# F6779_Ver_2_1.net
KiCad netlist of a schematic drawn in EAGLE
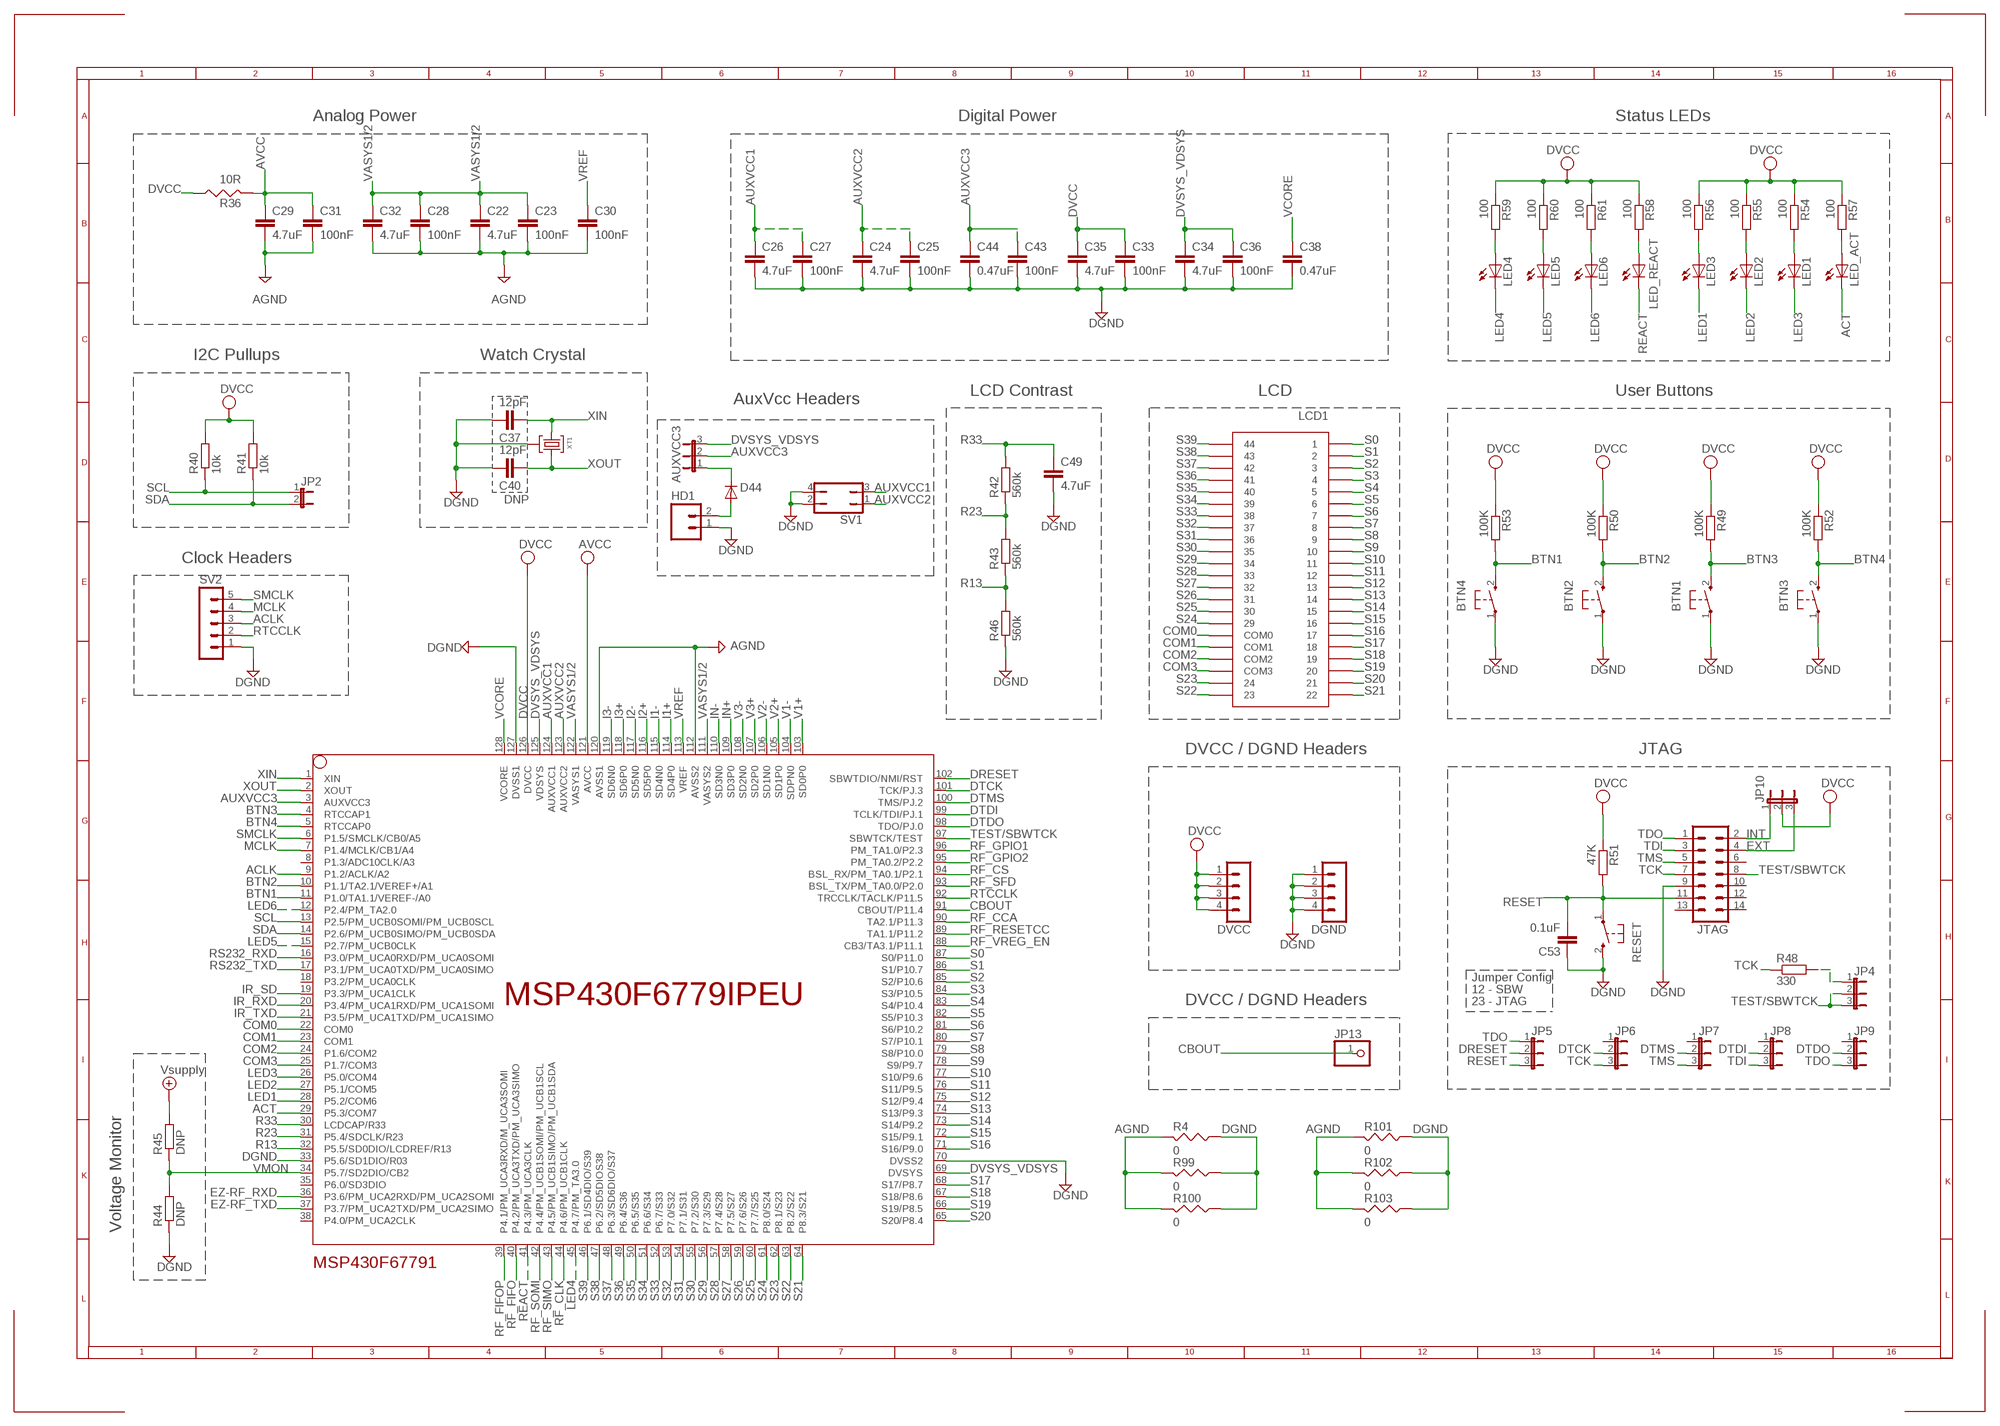
[diagram p0: schematic, sheet 1]
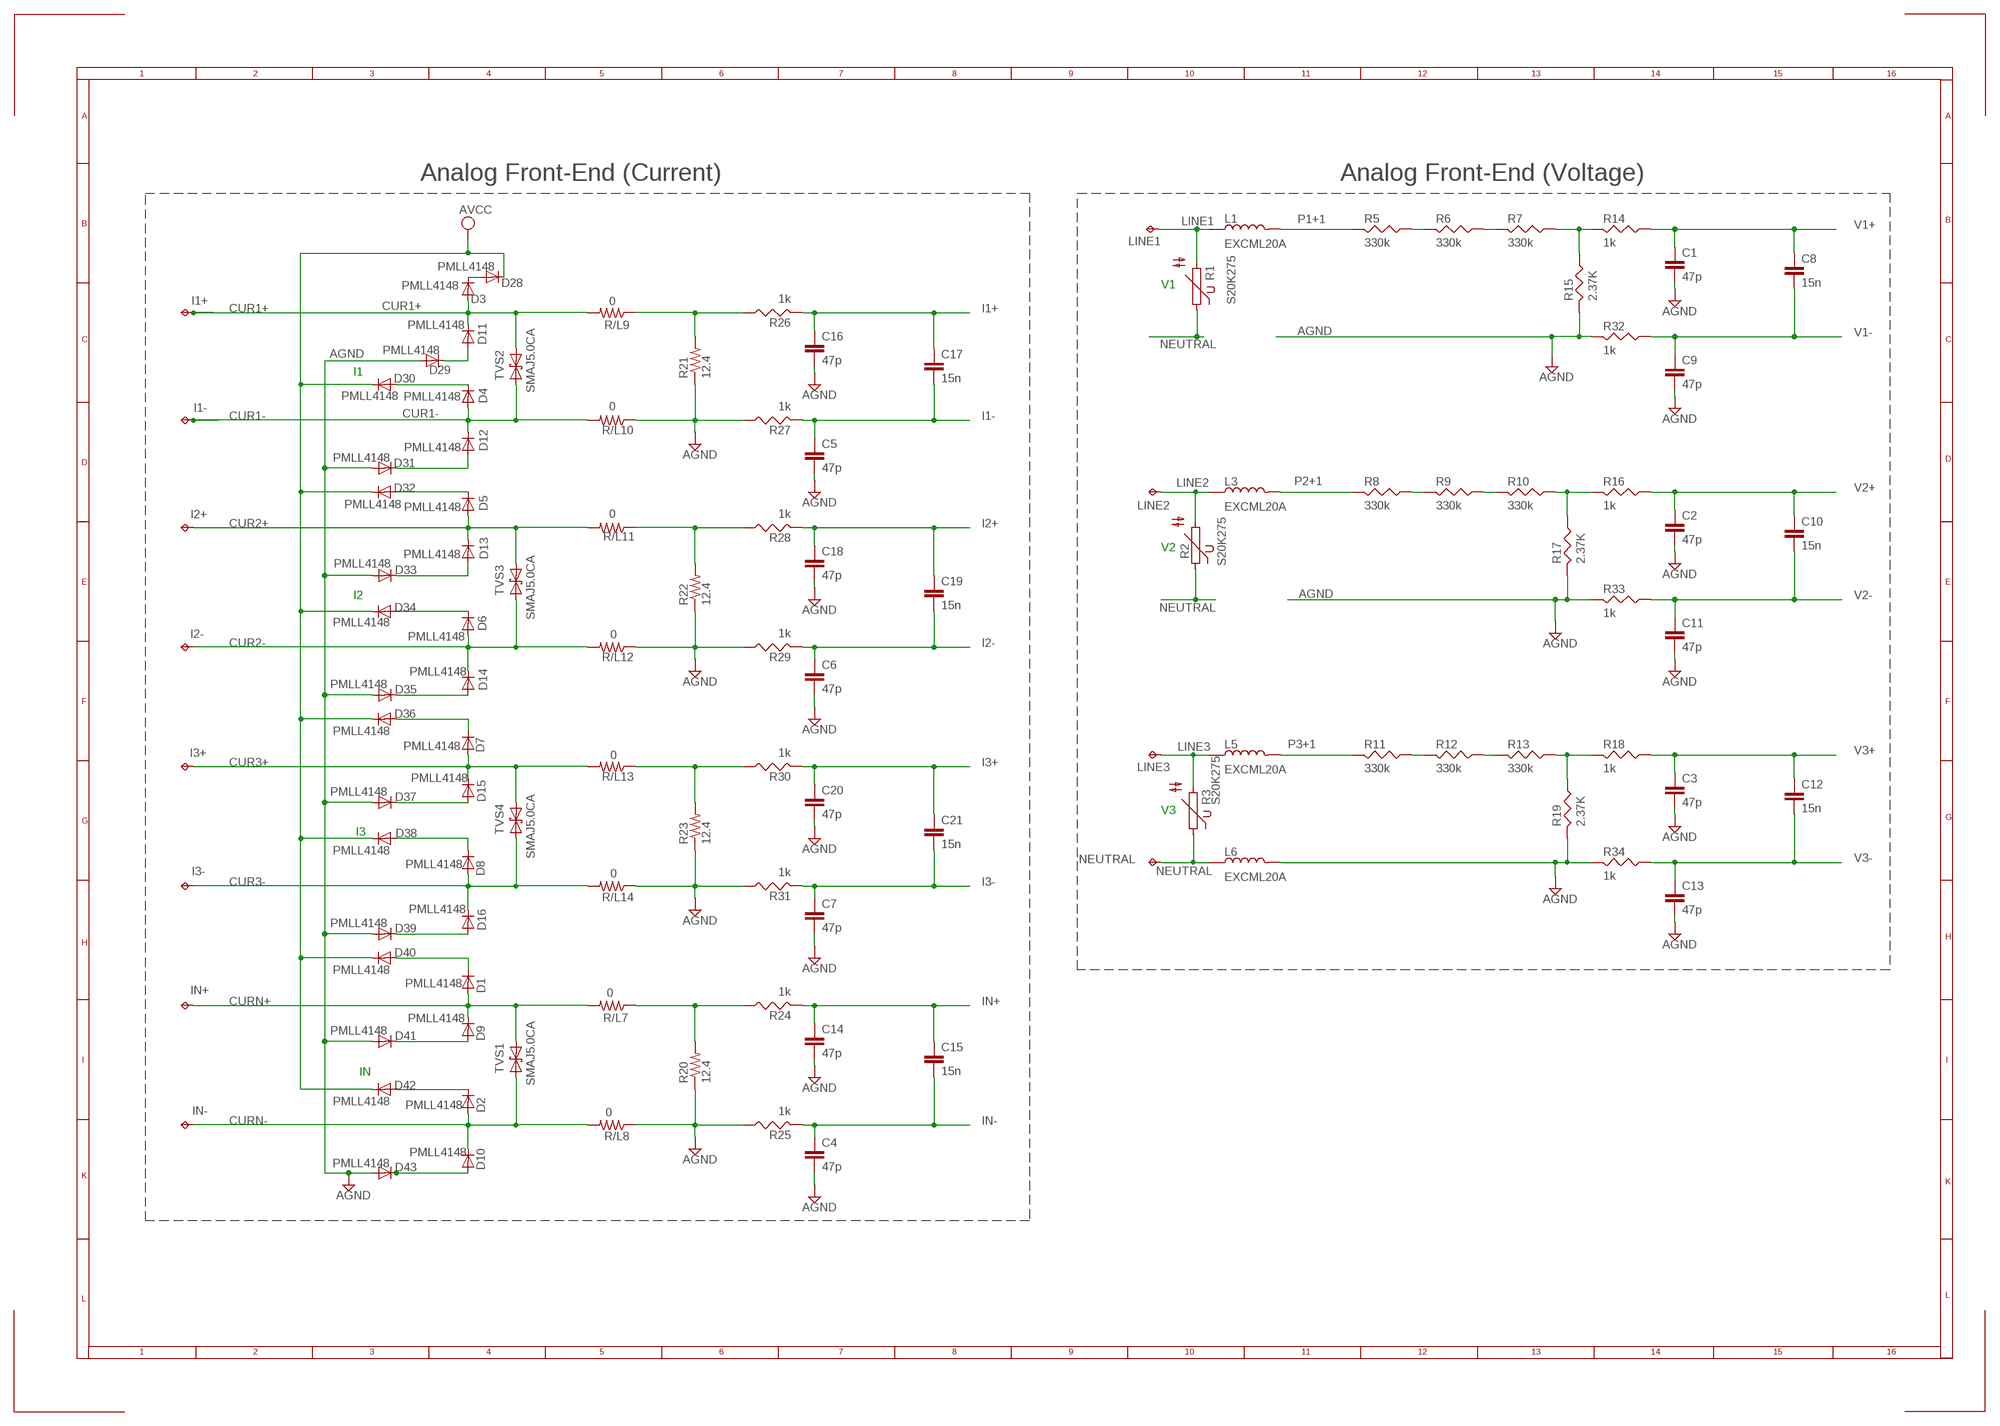
[diagram p1: schematic, sheet 2]
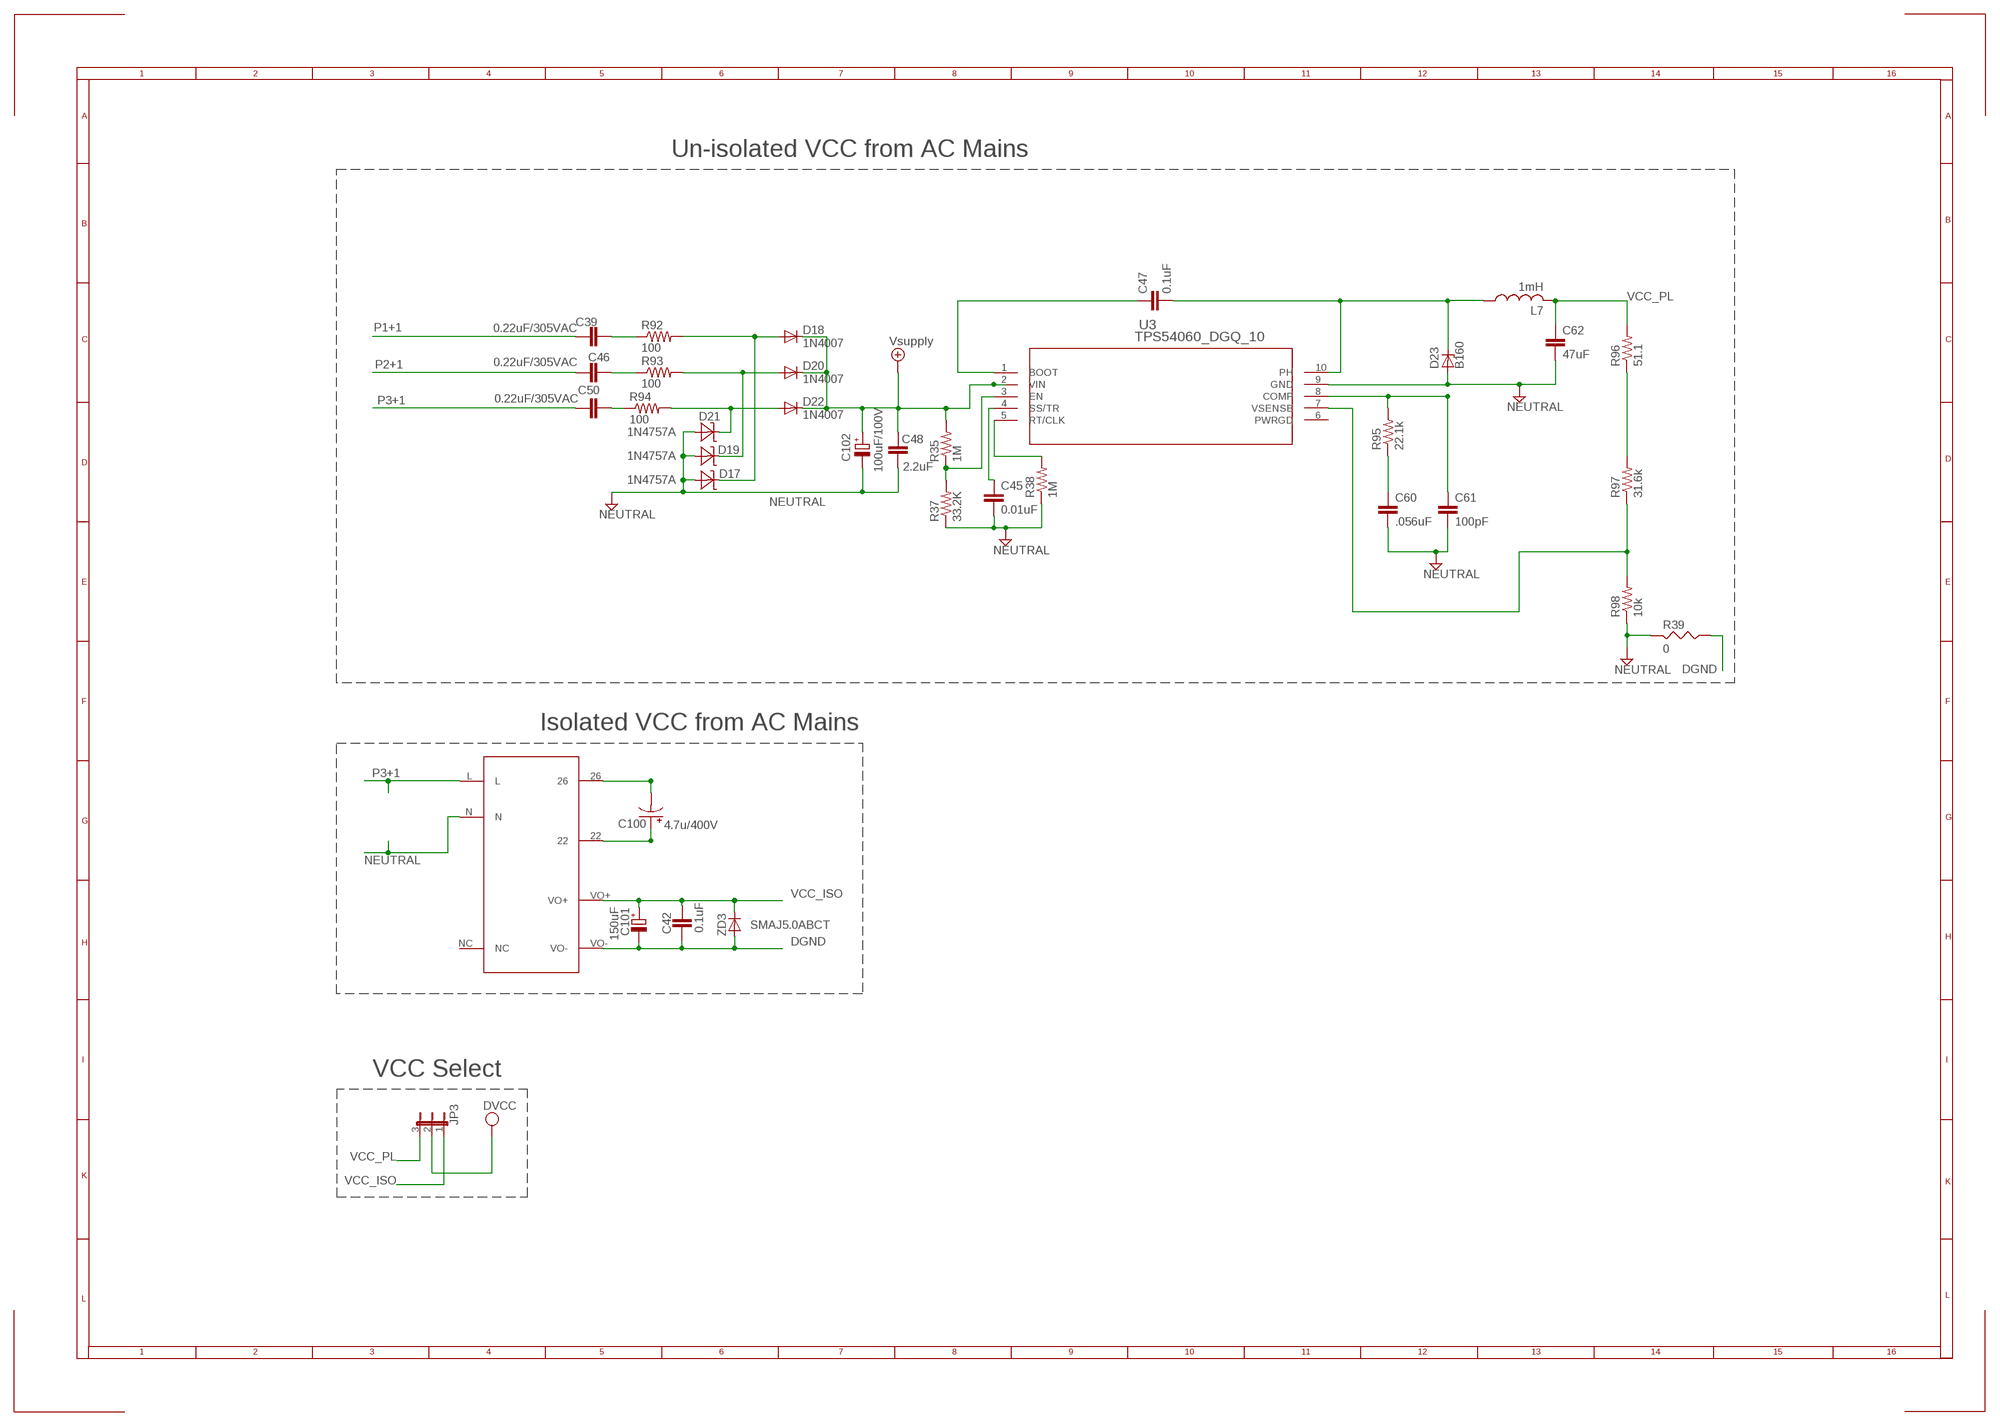
[diagram p2: schematic, sheet 3]
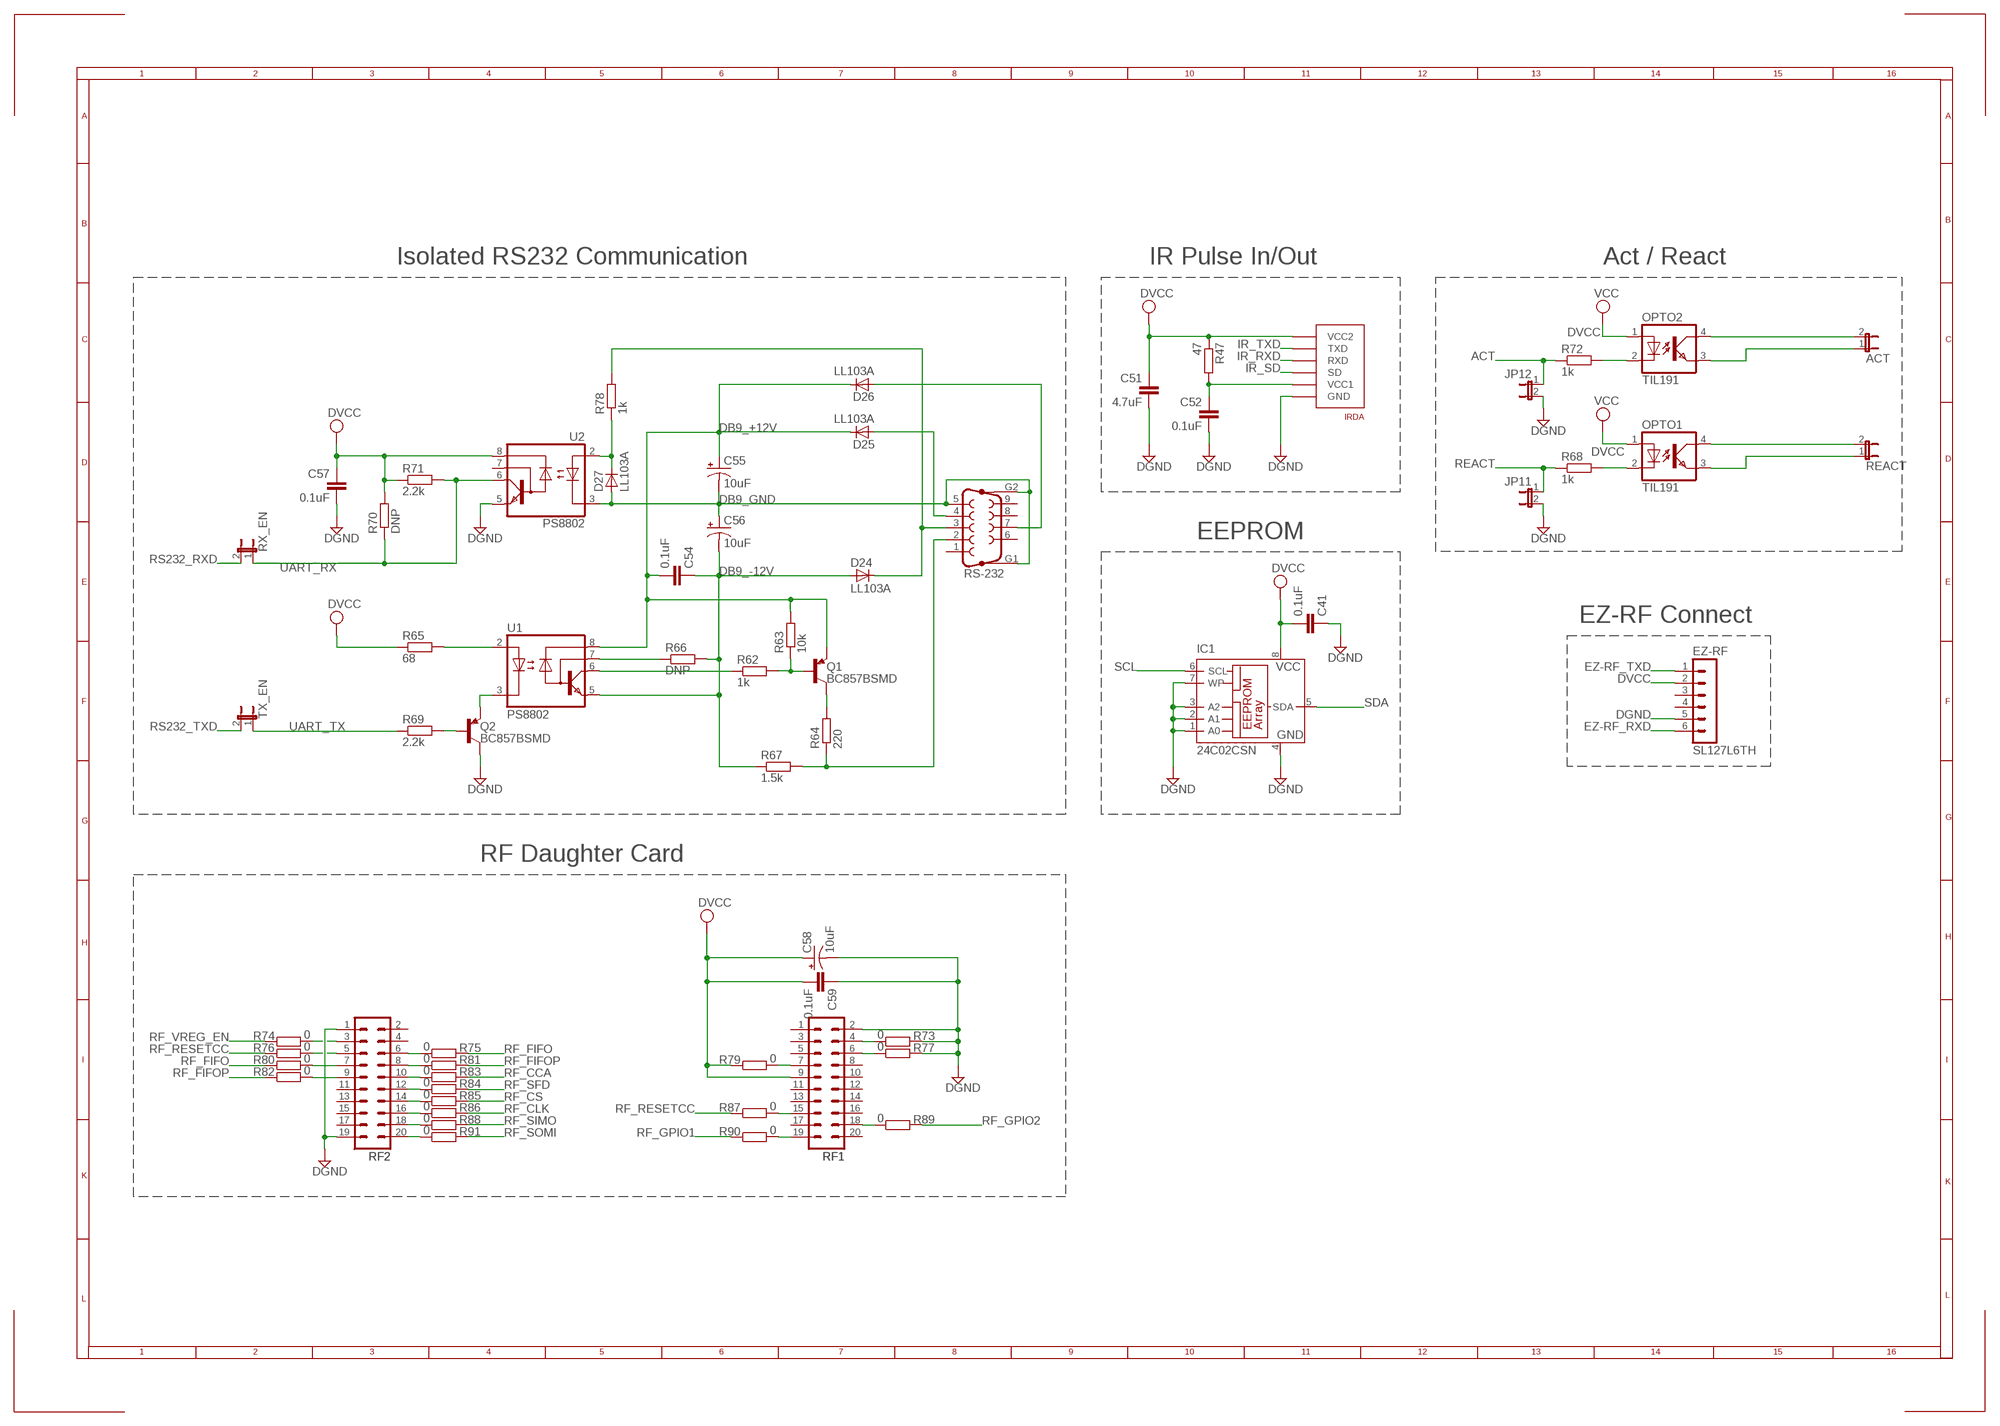
[diagram p3: schematic, sheet 4]

(export (version "E")
  (design (tool "Eeschema 10.0.6"))
  (components
    (comp (ref "ACT")
      (value "JP1E")
      (footprint "eagle-import:JP1")
      (libsource (lib "eagle-import") (part "JP1E"))
    )
    (comp (ref "C41")
      (value "0.1uF")
      (footprint "eagle-import:C0603")
      (libsource (lib "eagle-import") (part "C-EUC0603"))
    )
    (comp (ref "C51")
      (value "4.7uF")
      (footprint "eagle-import:C0603")
      (libsource (lib "eagle-import") (part "C-EUC0603"))
    )
    (comp (ref "C52")
      (value "0.1uF")
      (footprint "eagle-import:C0603")
      (libsource (lib "eagle-import") (part "C-EUC0603"))
    )
    (comp (ref "C54")
      (value "0.1uF")
      (footprint "eagle-import:C0603")
      (libsource (lib "eagle-import") (part "C-EUC0603"))
    )
    (comp (ref "C55")
      (value "10uF")
      (footprint "eagle-import:CT3216")
      (libsource (lib "eagle-import") (part "resistor_CPOL-USCT3216"))
    )
    (comp (ref "C56")
      (value "10uF")
      (footprint "eagle-import:CT3216")
      (libsource (lib "eagle-import") (part "resistor_CPOL-USCT3216"))
    )
    (comp (ref "C57")
      (value "0.1uF")
      (footprint "eagle-import:C0603")
      (libsource (lib "eagle-import") (part "C-EUC0603"))
    )
    (comp (ref "C58")
      (value "10uF")
      (footprint "eagle-import:CT3216")
      (libsource (lib "eagle-import") (part "CPOL-USCT3216"))
    )
    (comp (ref "C59")
      (value "0.1uF")
      (footprint "eagle-import:C0603")
      (libsource (lib "eagle-import") (part "resistor_C-EUC0603"))
    )
    (comp (ref "D24")
      (value "LL103A")
      (footprint "eagle-import:SOD80")
      (libsource (lib "eagle-import") (part "D-SOD-80"))
    )
    (comp (ref "D25")
      (value "LL103A")
      (footprint "eagle-import:SOD80")
      (libsource (lib "eagle-import") (part "D-SOD-80"))
    )
    (comp (ref "D26")
      (value "LL103A")
      (footprint "eagle-import:SOD80")
      (libsource (lib "eagle-import") (part "D-SOD-80"))
    )
    (comp (ref "D27")
      (value "LL103A")
      (footprint "eagle-import:SOD80")
      (libsource (lib "eagle-import") (part "D-SOD-80"))
    )
    (comp (ref "EZ-RF")
      (value "SL127L6TH")
      (footprint "eagle-import:SL127L6_MPE")
      (libsource (lib "eagle-import") (part "SL127L6TH"))
    )
    (comp (ref "IC1")
      (value "24C02CSN")
      (footprint "eagle-import:SO-08")
      (fields (field (name "MF") "MICROCHIP") (field (name "MPN") "24C02C/SN"))
      (libsource (lib "eagle-import") (part "24CSN02C"))
    )
    (comp (ref "IRDA")
      (value "TFBS4711-TT1")
      (footprint "eagle-import:TFBS4711")
      (libsource (lib "eagle-import") (part "TFBS4711-TT1"))
    )
    (comp (ref "JP11")
      (value "JP1E")
      (footprint "eagle-import:JP1")
      (libsource (lib "eagle-import") (part "JP1E"))
    )
    (comp (ref "JP12")
      (value "JP1E")
      (footprint "eagle-import:JP1")
      (libsource (lib "eagle-import") (part "JP1E"))
    )
    (comp (ref "OPTO1")
      (value "TIL191")
      (footprint "eagle-import:DIL04")
      (libsource (lib "eagle-import") (part "TIL191"))
    )
    (comp (ref "OPTO2")
      (value "TIL191")
      (footprint "eagle-import:DIL04")
      (libsource (lib "eagle-import") (part "TIL191"))
    )
    (comp (ref "Q1")
      (value "BC857BSMD")
      (footprint "eagle-import:SOT23-BEC")
      (libsource (lib "eagle-import") (part "BC857SMDB"))
    )
    (comp (ref "Q2")
      (value "BC857BSMD")
      (footprint "eagle-import:SOT23-BEC")
      (libsource (lib "eagle-import") (part "BC857SMDB"))
    )
    (comp (ref "R47")
      (value "47")
      (footprint "eagle-import:R0603")
      (libsource (lib "eagle-import") (part "R-EU_R0603"))
    )
    (comp (ref "R62")
      (value "1k")
      (footprint "eagle-import:R0603")
      (libsource (lib "eagle-import") (part "R-EU_R0603"))
    )
    (comp (ref "R63")
      (value "10k")
      (footprint "eagle-import:R0603")
      (libsource (lib "eagle-import") (part "R-EU_R0603"))
    )
    (comp (ref "R64")
      (value "220")
      (footprint "eagle-import:R0603")
      (libsource (lib "eagle-import") (part "R-EU_R0603"))
    )
    (comp (ref "R65")
      (value "68")
      (footprint "eagle-import:R0603")
      (libsource (lib "eagle-import") (part "R-EU_R0603"))
    )
    (comp (ref "R66")
      (value "DNP")
      (footprint "eagle-import:R0603")
      (libsource (lib "eagle-import") (part "R-EU_R0603"))
    )
    (comp (ref "R67")
      (value "1.5k")
      (footprint "eagle-import:R0603")
      (libsource (lib "eagle-import") (part "R-EU_R0603"))
    )
    (comp (ref "R68")
      (value "1k")
      (footprint "eagle-import:R0603")
      (libsource (lib "eagle-import") (part "R-EU_R0603"))
    )
    (comp (ref "R69")
      (value "2.2k")
      (footprint "eagle-import:R0603")
      (libsource (lib "eagle-import") (part "R-EU_R0603"))
    )
    (comp (ref "R70")
      (value "DNP")
      (footprint "eagle-import:R0603")
      (libsource (lib "eagle-import") (part "R-EU_R0603"))
    )
    (comp (ref "R71")
      (value "2.2k")
      (footprint "eagle-import:R0603")
      (libsource (lib "eagle-import") (part "R-EU_R0603"))
    )
    (comp (ref "R72")
      (value "1k")
      (footprint "eagle-import:R0603")
      (libsource (lib "eagle-import") (part "R-EU_R0603"))
    )
    (comp (ref "R73")
      (value "0")
      (footprint "eagle-import:R0603")
      (libsource (lib "eagle-import") (part "R-EU_R0603"))
    )
    (comp (ref "R74")
      (value "0")
      (footprint "eagle-import:R0603")
      (libsource (lib "eagle-import") (part "R-EU_R0603"))
    )
    (comp (ref "R75")
      (value "0")
      (footprint "eagle-import:R0603")
      (libsource (lib "eagle-import") (part "R-EU_R0603"))
    )
    (comp (ref "R76")
      (value "0")
      (footprint "eagle-import:R0603")
      (libsource (lib "eagle-import") (part "R-EU_R0603"))
    )
    (comp (ref "R77")
      (value "0")
      (footprint "eagle-import:R0603")
      (libsource (lib "eagle-import") (part "R-EU_R0603"))
    )
    (comp (ref "R78")
      (value "1k")
      (footprint "eagle-import:R0603")
      (libsource (lib "eagle-import") (part "R-EU_R0603"))
    )
    (comp (ref "R79")
      (value "0")
      (footprint "eagle-import:R0603")
      (libsource (lib "eagle-import") (part "R-EU_R0603"))
    )
    (comp (ref "R80")
      (value "0")
      (footprint "eagle-import:R0603")
      (libsource (lib "eagle-import") (part "R-EU_R0603"))
    )
    (comp (ref "R81")
      (value "0")
      (footprint "eagle-import:R0603")
      (libsource (lib "eagle-import") (part "R-EU_R0603"))
    )
    (comp (ref "R82")
      (value "0")
      (footprint "eagle-import:R0603")
      (libsource (lib "eagle-import") (part "R-EU_R0603"))
    )
    (comp (ref "R83")
      (value "0")
      (footprint "eagle-import:R0603")
      (libsource (lib "eagle-import") (part "R-EU_R0603"))
    )
    (comp (ref "R84")
      (value "0")
      (footprint "eagle-import:R0603")
      (libsource (lib "eagle-import") (part "R-EU_R0603"))
    )
    (comp (ref "R85")
      (value "0")
      (footprint "eagle-import:R0603")
      (libsource (lib "eagle-import") (part "R-EU_R0603"))
    )
    (comp (ref "R86")
      (value "0")
      (footprint "eagle-import:R0603")
      (libsource (lib "eagle-import") (part "R-EU_R0603"))
    )
    (comp (ref "R87")
      (value "0")
      (footprint "eagle-import:R0603")
      (libsource (lib "eagle-import") (part "R-EU_R0603"))
    )
    (comp (ref "R88")
      (value "0")
      (footprint "eagle-import:R0603")
      (libsource (lib "eagle-import") (part "R-EU_R0603"))
    )
    (comp (ref "R89")
      (value "0")
      (footprint "eagle-import:R0603")
      (libsource (lib "eagle-import") (part "R-EU_R0603"))
    )
    (comp (ref "R90")
      (value "0")
      (footprint "eagle-import:R0603")
      (libsource (lib "eagle-import") (part "R-EU_R0603"))
    )
    (comp (ref "R91")
      (value "0")
      (footprint "eagle-import:R0603")
      (libsource (lib "eagle-import") (part "R-EU_R0603"))
    )
    (comp (ref "REACT")
      (value "JP1E")
      (footprint "eagle-import:JP1")
      (libsource (lib "eagle-import") (part "JP1E"))
    )
    (comp (ref "RF1")
      (value "TFM-110-02-SM-D-A-K")
      (footprint "eagle-import:TFM-110-02-SM-D-A-K")
      (libsource (lib "eagle-import") (part "TFM-110-02-SM-D-A-K"))
    )
    (comp (ref "RF2")
      (value "TFM-110-02-SM-D-A-K")
      (footprint "eagle-import:TFM-110-02-SM-D-A-K")
      (libsource (lib "eagle-import") (part "TFM-110-02-SM-D-A-K"))
    )
    (comp (ref "RS-232")
      (value "F09VP")
      (footprint "eagle-import:F09VP")
      (libsource (lib "eagle-import") (part "F09VP"))
    )
    (comp (ref "RX_EN")
      (value "JP1E")
      (footprint "eagle-import:JP1")
      (libsource (lib "eagle-import") (part "JP1E"))
    )
    (comp (ref "TX_EN")
      (value "JP1E")
      (footprint "eagle-import:JP1")
      (libsource (lib "eagle-import") (part "JP1E"))
    )
    (comp (ref "U1")
      (value "PS8802")
      (footprint "eagle-import:SO08")
      (libsource (lib "eagle-import") (part "PS8802"))
    )
    (comp (ref "U2")
      (value "PS8802")
      (footprint "eagle-import:SO08")
      (libsource (lib "eagle-import") (part "PS8802"))
    )
    (comp (ref "C39")
      (value "0.22uF/305VAC")
      (footprint "eagle-import:C15B8")
      (libsource (lib "eagle-import") (part "C15/8"))
    )
    (comp (ref "C42")
      (value "0.1uF")
      (footprint "eagle-import:C0603")
      (libsource (lib "eagle-import") (part "resistor_C-EUC0603"))
    )
    (comp (ref "C45")
      (value "0.01uF")
      (footprint "eagle-import:C0603")
      (libsource (lib "eagle-import") (part "C-EUC0603"))
    )
    (comp (ref "C46")
      (value "0.22uF/305VAC")
      (footprint "eagle-import:C15B8")
      (libsource (lib "eagle-import") (part "C15/8"))
    )
    (comp (ref "C47")
      (value "0.1uF")
      (footprint "eagle-import:C0603")
      (libsource (lib "eagle-import") (part "C-EUC0603"))
    )
    (comp (ref "C48")
      (value "2.2uF")
      (footprint "eagle-import:C1210")
      (libsource (lib "eagle-import") (part "resistor_C-EUC1210"))
    )
    (comp (ref "C50")
      (value "0.22uF/305VAC")
      (footprint "eagle-import:C15B8")
      (libsource (lib "eagle-import") (part "C15/8"))
    )
    (comp (ref "C60")
      (value ".056uF")
      (footprint "eagle-import:C0603")
      (libsource (lib "eagle-import") (part "resistor_C-EUC0603"))
    )
    (comp (ref "C61")
      (value "100pF")
      (footprint "eagle-import:C0603")
      (libsource (lib "eagle-import") (part "resistor_C-EUC0603"))
    )
    (comp (ref "C62")
      (value "47uF")
      (footprint "eagle-import:C1210")
      (libsource (lib "eagle-import") (part "C-EUC1210"))
    )
    (comp (ref "C100")
      (value "4.7u/400V")
      (footprint "eagle-import:E5-10,5")
      (libsource (lib "eagle-import") (part "CPOL-USE5-10.5"))
    )
    (comp (ref "C101")
      (value "150uF")
      (footprint "eagle-import:E2-5")
      (libsource (lib "eagle-import") (part "CPOL-EUE2-5"))
    )
    (comp (ref "C102")
      (value "100uF/100V")
      (footprint "eagle-import:E5-10,5")
      (libsource (lib "eagle-import") (part "resistor_CPOL-EUE5-10.5"))
    )
    (comp (ref "D17")
      (value "1N4757A")
      (footprint "eagle-import:DO41Z10")
      (libsource (lib "eagle-import") (part "1N4757A"))
    )
    (comp (ref "D18")
      (value "1N4007")
      (footprint "eagle-import:DO41-10")
      (libsource (lib "eagle-import") (part "1N4007"))
    )
    (comp (ref "D19")
      (value "1N4757A")
      (footprint "eagle-import:DO41Z10")
      (libsource (lib "eagle-import") (part "1N4757A"))
    )
    (comp (ref "D20")
      (value "1N4007")
      (footprint "eagle-import:DO41-10")
      (libsource (lib "eagle-import") (part "1N4007"))
    )
    (comp (ref "D21")
      (value "1N4757A")
      (footprint "eagle-import:DO41Z10")
      (libsource (lib "eagle-import") (part "1N4757A"))
    )
    (comp (ref "D22")
      (value "1N4007")
      (footprint "eagle-import:DO41-10")
      (libsource (lib "eagle-import") (part "1N4007"))
    )
    (comp (ref "D23")
      (value "B160")
      (footprint "eagle-import:SMB")
      (libsource (lib "eagle-import") (part "ZENER-DIODESMB"))
    )
    (comp (ref "JP3")
      (value "JP2E")
      (footprint "eagle-import:JP2")
      (libsource (lib "eagle-import") (part "JP2E"))
    )
    (comp (ref "L7")
      (value "1mH")
      (footprint "eagle-import:INDUCTOR_POWER_SUPPLY_6779")
      (libsource (lib "eagle-import") (part "L-USMSS1038-105"))
    )
    (comp (ref "R35")
      (value "1M")
      (footprint "eagle-import:R0603")
      (libsource (lib "eagle-import") (part "resistor_R-US_R0603"))
    )
    (comp (ref "R37")
      (value "33.2K")
      (footprint "eagle-import:R0603")
      (libsource (lib "eagle-import") (part "resistor_R-US_R0603"))
    )
    (comp (ref "R38")
      (value "1M")
      (footprint "eagle-import:R0603")
      (libsource (lib "eagle-import") (part "resistor_R-US_R0603"))
    )
    (comp (ref "R39")
      (value "0")
      (footprint "eagle-import:R0805")
      (libsource (lib "eagle-import") (part "RES0805"))
    )
    (comp (ref "R92")
      (value "100")
      (footprint "eagle-import:0414_15")
      (libsource (lib "eagle-import") (part "resistor_R-US_0414/15"))
    )
    (comp (ref "R93")
      (value "100")
      (footprint "eagle-import:0414_15")
      (libsource (lib "eagle-import") (part "resistor_R-US_0414/15"))
    )
    (comp (ref "R94")
      (value "100")
      (footprint "eagle-import:0414_15")
      (libsource (lib "eagle-import") (part "resistor_R-US_0414/15"))
    )
    (comp (ref "R95")
      (value "22.1k")
      (footprint "eagle-import:R0603")
      (libsource (lib "eagle-import") (part "resistor_R-US_R0603"))
    )
    (comp (ref "R96")
      (value "51.1")
      (footprint "eagle-import:R0603")
      (libsource (lib "eagle-import") (part "R-US_R0603"))
    )
    (comp (ref "R97")
      (value "31.6k")
      (footprint "eagle-import:R0603")
      (libsource (lib "eagle-import") (part "R-US_R0603"))
    )
    (comp (ref "R98")
      (value "10k")
      (footprint "eagle-import:R0603")
      (libsource (lib "eagle-import") (part "R-US_R0603"))
    )
    (comp (ref "U$1")
      (value "CUI_XR")
      (footprint "eagle-import:CUI_XR")
      (libsource (lib "eagle-import") (part "CUI_XR"))
    )
    (comp (ref "U3")
      (value "TPS54060_DGQ_10")
      (footprint "eagle-import:DGQ10_1P88X1P57")
      (fields
        (field (name "GENERIC_PART_NUMBER") "TPS54060")
        (field (name "MANUFACTURER") "Texas Instruments")
        (field (name "MANUFACTURER_PART_NUMBER") "tps54060_dgq_10")
      )
      (libsource (lib "eagle-import") (part "TPS54060_DGQ_10"))
    )
    (comp (ref "ZD3")
      (value "SMAJ5.0ABCT")
      (footprint "eagle-import:DO214AC")
      (libsource (lib "eagle-import") (part "DIODE-DO214AC"))
    )
    (comp (ref "AUXVCC3")
      (value "JP2E")
      (footprint "eagle-import:JP2")
      (libsource (lib "eagle-import") (part "jumper_JP2E"))
    )
    (comp (ref "BTN1")
      (value "PB")
      (footprint "eagle-import:PBTH")
      (libsource (lib "eagle-import") (part "PB"))
    )
    (comp (ref "BTN2")
      (value "PB")
      (footprint "eagle-import:PBTH")
      (libsource (lib "eagle-import") (part "PB"))
    )
    (comp (ref "BTN3")
      (value "PB")
      (footprint "eagle-import:PBTH")
      (libsource (lib "eagle-import") (part "PB"))
    )
    (comp (ref "BTN4")
      (value "PB")
      (footprint "eagle-import:PBTH")
      (libsource (lib "eagle-import") (part "PB"))
    )
    (comp (ref "C22")
      (value "4.7uF")
      (footprint "eagle-import:C0603")
      (libsource (lib "eagle-import") (part "resistor_C-EUC0603"))
    )
    (comp (ref "C23")
      (value "100nF")
      (footprint "eagle-import:C0603")
      (libsource (lib "eagle-import") (part "resistor_C-EUC0603"))
    )
    (comp (ref "C24")
      (value "4.7uF")
      (footprint "eagle-import:C0603")
      (libsource (lib "eagle-import") (part "resistor_C-EUC0603"))
    )
    (comp (ref "C25")
      (value "100nF")
      (footprint "eagle-import:C0603")
      (libsource (lib "eagle-import") (part "resistor_C-EUC0603"))
    )
    (comp (ref "C26")
      (value "4.7uF")
      (footprint "eagle-import:C0603")
      (libsource (lib "eagle-import") (part "resistor_C-EUC0603"))
    )
    (comp (ref "C27")
      (value "100nF")
      (footprint "eagle-import:C0603")
      (libsource (lib "eagle-import") (part "resistor_C-EUC0603"))
    )
    (comp (ref "C28")
      (value "100nF")
      (footprint "eagle-import:C0603")
      (libsource (lib "eagle-import") (part "resistor_C-EUC0603"))
    )
    (comp (ref "C29")
      (value "4.7uF")
      (footprint "eagle-import:C0603")
      (libsource (lib "eagle-import") (part "resistor_C-EUC0603"))
    )
    (comp (ref "C30")
      (value "100nF")
      (footprint "eagle-import:C0603")
      (libsource (lib "eagle-import") (part "resistor_C-EUC0603"))
    )
    (comp (ref "C31")
      (value "100nF")
      (footprint "eagle-import:C0603")
      (libsource (lib "eagle-import") (part "resistor_C-EUC0603"))
    )
    (comp (ref "C32")
      (value "4.7uF")
      (footprint "eagle-import:C0603")
      (libsource (lib "eagle-import") (part "resistor_C-EUC0603"))
    )
    (comp (ref "C33")
      (value "100nF")
      (footprint "eagle-import:C0603")
      (libsource (lib "eagle-import") (part "resistor_C-EUC0603"))
    )
    (comp (ref "C34")
      (value "4.7uF")
      (footprint "eagle-import:C0603")
      (libsource (lib "eagle-import") (part "resistor_C-EUC0603"))
    )
    (comp (ref "C35")
      (value "4.7uF")
      (footprint "eagle-import:C0603")
      (libsource (lib "eagle-import") (part "resistor_C-EUC0603"))
    )
    (comp (ref "C36")
      (value "100nF")
      (footprint "eagle-import:C0603")
      (libsource (lib "eagle-import") (part "resistor_C-EUC0603"))
    )
    (comp (ref "C37")
      (value "12pF")
      (footprint "eagle-import:C0603")
      (libsource (lib "eagle-import") (part "resistor_C-EUC0603"))
    )
    (comp (ref "C38")
      (value "0.47uF")
      (footprint "eagle-import:C0603")
      (libsource (lib "eagle-import") (part "resistor_C-EUC0603"))
    )
    (comp (ref "C40")
      (value "12pF")
      (footprint "eagle-import:C0603")
      (libsource (lib "eagle-import") (part "resistor_C-EUC0603"))
    )
    (comp (ref "C43")
      (value "100nF")
      (footprint "eagle-import:C0603")
      (libsource (lib "eagle-import") (part "resistor_C-EUC0603"))
    )
    (comp (ref "C44")
      (value "0.47uF")
      (footprint "eagle-import:C0603")
      (libsource (lib "eagle-import") (part "resistor_C-EUC0603"))
    )
    (comp (ref "C49")
      (value "4.7uF")
      (footprint "eagle-import:C0603")
      (libsource (lib "eagle-import") (part "resistor_C-EUC0603"))
    )
    (comp (ref "C53")
      (value "0.1uF")
      (footprint "eagle-import:C0603")
      (libsource (lib "eagle-import") (part "resistor_C-EUC0603"))
    )
    (comp (ref "D44")
      (value "PMLL4148")
      (footprint "eagle-import:SOD80C")
      (libsource (lib "eagle-import") (part "PMLL4148"))
    )
    (comp (ref "DGND")
      (value "MA04-1")
      (footprint "eagle-import:MA04-1")
      (libsource (lib "eagle-import") (part "MA04-1"))
    )
    (comp (ref "DVCC")
      (value "MA04-1")
      (footprint "eagle-import:MA04-1")
      (libsource (lib "eagle-import") (part "MA04-1"))
    )
    (comp (ref "HD1")
      (value "M02PTH")
      (footprint "eagle-import:1X02")
      (libsource (lib "eagle-import") (part "M02PTH"))
    )
    (comp (ref "JP2")
      (value "JP1E")
      (footprint "eagle-import:JP1")
      (libsource (lib "eagle-import") (part "JP1E"))
    )
    (comp (ref "JP4")
      (value "JP2E")
      (footprint "eagle-import:JP2")
      (libsource (lib "eagle-import") (part "JP2E"))
    )
    (comp (ref "JP5")
      (value "JP2E")
      (footprint "eagle-import:JP2")
      (libsource (lib "eagle-import") (part "JP2E"))
    )
    (comp (ref "JP6")
      (value "JP2E")
      (footprint "eagle-import:JP2")
      (libsource (lib "eagle-import") (part "JP2E"))
    )
    (comp (ref "JP7")
      (value "JP2E")
      (footprint "eagle-import:JP2")
      (libsource (lib "eagle-import") (part "JP2E"))
    )
    (comp (ref "JP8")
      (value "JP2E")
      (footprint "eagle-import:JP2")
      (libsource (lib "eagle-import") (part "JP2E"))
    )
    (comp (ref "JP9")
      (value "JP2E")
      (footprint "eagle-import:JP2")
      (libsource (lib "eagle-import") (part "JP2E"))
    )
    (comp (ref "JP10")
      (value "JP2E")
      (footprint "eagle-import:JP2")
      (libsource (lib "eagle-import") (part "JP2E"))
    )
    (comp (ref "JP13")
      (value "PINHD-1X1")
      (footprint "eagle-import:1X01")
      (libsource (lib "eagle-import") (part "PINHD-1X1"))
    )
    (comp (ref "JTAG")
      (value "ML14")
      (footprint "eagle-import:ML14")
      (libsource (lib "eagle-import") (part "ML14"))
    )
    (comp (ref "LCD1")
      (value "TI_160SEG_LCD")
      (footprint "eagle-import:TI_160SEG_LCD")
      (libsource (lib "eagle-import") (part "TI_160SEG_LCD"))
    )
    (comp (ref "LED1")
      (value "LED3MM")
      (footprint "eagle-import:LED3MM")
      (libsource (lib "eagle-import") (part "LED3MM"))
    )
    (comp (ref "LED2")
      (value "LED3MM")
      (footprint "eagle-import:LED3MM")
      (libsource (lib "eagle-import") (part "LED3MM"))
    )
    (comp (ref "LED3")
      (value "LED3MM")
      (footprint "eagle-import:LED3MM")
      (libsource (lib "eagle-import") (part "LED3MM"))
    )
    (comp (ref "LED4")
      (value "LED3MM")
      (footprint "eagle-import:LED3MM")
      (libsource (lib "eagle-import") (part "LED3MM"))
    )
    (comp (ref "LED5")
      (value "LED3MM")
      (footprint "eagle-import:LED3MM")
      (libsource (lib "eagle-import") (part "LED3MM"))
    )
    (comp (ref "LED6")
      (value "LED3MM")
      (footprint "eagle-import:LED3MM")
      (libsource (lib "eagle-import") (part "LED3MM"))
    )
    (comp (ref "LED_ACT")
      (value "LED3MM")
      (footprint "eagle-import:LED3MM")
      (libsource (lib "eagle-import") (part "LED3MM"))
    )
    (comp (ref "LED_REACT")
      (value "LED3MM")
      (footprint "eagle-import:LED3MM")
      (libsource (lib "eagle-import") (part "LED3MM"))
    )
    (comp (ref "MSP430F67791")
      (value "MSP430F6779IPEU")
      (footprint "eagle-import:PEU128")
      (libsource (lib "eagle-import") (part "MSP430F6779IPEU"))
    )
    (comp (ref "R4")
      (value "0")
      (footprint "eagle-import:R0805")
      (libsource (lib "eagle-import") (part "RES0805"))
    )
    (comp (ref "R36")
      (value "10R")
      (footprint "eagle-import:R0805")
      (libsource (lib "eagle-import") (part "RES0805"))
    )
    (comp (ref "R40")
      (value "10k")
      (footprint "eagle-import:R0603")
      (libsource (lib "eagle-import") (part "R-EU_R0603"))
    )
    (comp (ref "R41")
      (value "10k")
      (footprint "eagle-import:R0603")
      (libsource (lib "eagle-import") (part "R-EU_R0603"))
    )
    (comp (ref "R42")
      (value "560k")
      (footprint "eagle-import:R0603")
      (libsource (lib "eagle-import") (part "resistor_R-EU_R0603"))
    )
    (comp (ref "R43")
      (value "560k")
      (footprint "eagle-import:R0603")
      (libsource (lib "eagle-import") (part "resistor_R-EU_R0603"))
    )
    (comp (ref "R44")
      (value "DNP")
      (footprint "eagle-import:R0603")
      (libsource (lib "eagle-import") (part "resistor_R-EU_R0603"))
    )
    (comp (ref "R45")
      (value "DNP")
      (footprint "eagle-import:R0603")
      (libsource (lib "eagle-import") (part "resistor_R-EU_R0603"))
    )
    (comp (ref "R46")
      (value "560k")
      (footprint "eagle-import:R0603")
      (libsource (lib "eagle-import") (part "resistor_R-EU_R0603"))
    )
    (comp (ref "R48")
      (value "330")
      (footprint "eagle-import:R0603")
      (libsource (lib "eagle-import") (part "resistor_R-EU_R0603"))
    )
    (comp (ref "R49")
      (value "100K")
      (footprint "eagle-import:R0603")
      (libsource (lib "eagle-import") (part "resistor_R-EU_R0603"))
    )
    (comp (ref "R50")
      (value "100K")
      (footprint "eagle-import:R0603")
      (libsource (lib "eagle-import") (part "resistor_R-EU_R0603"))
    )
    (comp (ref "R51")
      (value "47K")
      (footprint "eagle-import:R0603")
      (libsource (lib "eagle-import") (part "resistor_R-EU_R0603"))
    )
    (comp (ref "R52")
      (value "100K")
      (footprint "eagle-import:R0603")
      (libsource (lib "eagle-import") (part "resistor_R-EU_R0603"))
    )
    (comp (ref "R53")
      (value "100K")
      (footprint "eagle-import:R0603")
      (libsource (lib "eagle-import") (part "resistor_R-EU_R0603"))
    )
    (comp (ref "R54")
      (value "100")
      (footprint "eagle-import:R0603")
      (libsource (lib "eagle-import") (part "resistor_R-EU_R0603"))
    )
    (comp (ref "R55")
      (value "100")
      (footprint "eagle-import:R0603")
      (libsource (lib "eagle-import") (part "resistor_R-EU_R0603"))
    )
    (comp (ref "R56")
      (value "100")
      (footprint "eagle-import:R0603")
      (libsource (lib "eagle-import") (part "resistor_R-EU_R0603"))
    )
    (comp (ref "R57")
      (value "100")
      (footprint "eagle-import:R0603")
      (libsource (lib "eagle-import") (part "resistor_R-EU_R0603"))
    )
    (comp (ref "R58")
      (value "100")
      (footprint "eagle-import:R0603")
      (libsource (lib "eagle-import") (part "resistor_R-EU_R0603"))
    )
    (comp (ref "R59")
      (value "100")
      (footprint "eagle-import:R0603")
      (libsource (lib "eagle-import") (part "resistor_R-EU_R0603"))
    )
    (comp (ref "R60")
      (value "100")
      (footprint "eagle-import:R0603")
      (libsource (lib "eagle-import") (part "resistor_R-EU_R0603"))
    )
    (comp (ref "R61")
      (value "100")
      (footprint "eagle-import:R0603")
      (libsource (lib "eagle-import") (part "resistor_R-EU_R0603"))
    )
    (comp (ref "R99")
      (value "0")
      (footprint "eagle-import:R0805")
      (libsource (lib "eagle-import") (part "RES0805"))
    )
    (comp (ref "R100")
      (value "0")
      (footprint "eagle-import:R0805")
      (libsource (lib "eagle-import") (part "RES0805"))
    )
    (comp (ref "R101")
      (value "0")
      (footprint "eagle-import:R0805")
      (libsource (lib "eagle-import") (part "RES0805"))
    )
    (comp (ref "R102")
      (value "0")
      (footprint "eagle-import:R0805")
      (libsource (lib "eagle-import") (part "RES0805"))
    )
    (comp (ref "R103")
      (value "0")
      (footprint "eagle-import:R0805")
      (libsource (lib "eagle-import") (part "RES0805"))
    )
    (comp (ref "RESET")
      (value "PB")
      (footprint "eagle-import:PBTH")
      (libsource (lib "eagle-import") (part "PB"))
    )
    (comp (ref "SV1")
      (value "JP2Q")
      (footprint "eagle-import:JP2Q")
      (libsource (lib "eagle-import") (part "JP2Q"))
    )
    (comp (ref "SV2")
      (value "MA05-1")
      (footprint "eagle-import:MA05-1")
      (libsource (lib "eagle-import") (part "MA05-1"))
    )
    (comp (ref "XT1")
      (value "CM200T")
      (footprint "eagle-import:CM200T")
      (libsource (lib "eagle-import") (part "CM200T"))
    )
    (comp (ref "C1")
      (value "47p")
      (footprint "eagle-import:C0805")
      (libsource (lib "eagle-import") (part "C-EUC0805"))
    )
    (comp (ref "C2")
      (value "47p")
      (footprint "eagle-import:C0805")
      (libsource (lib "eagle-import") (part "C-EUC0805"))
    )
    (comp (ref "C3")
      (value "47p")
      (footprint "eagle-import:C0805")
      (libsource (lib "eagle-import") (part "C-EUC0805"))
    )
    (comp (ref "C4")
      (value "47p")
      (footprint "eagle-import:C0805")
      (libsource (lib "eagle-import") (part "C-EUC0805"))
    )
    (comp (ref "C5")
      (value "47p")
      (footprint "eagle-import:C0805")
      (libsource (lib "eagle-import") (part "C-EUC0805"))
    )
    (comp (ref "C6")
      (value "47p")
      (footprint "eagle-import:C0805")
      (libsource (lib "eagle-import") (part "C-EUC0805"))
    )
    (comp (ref "C7")
      (value "47p")
      (footprint "eagle-import:C0805")
      (libsource (lib "eagle-import") (part "C-EUC0805"))
    )
    (comp (ref "C8")
      (value "15n")
      (footprint "eagle-import:C0805")
      (libsource (lib "eagle-import") (part "C-EUC0805"))
    )
    (comp (ref "C9")
      (value "47p")
      (footprint "eagle-import:C0805")
      (libsource (lib "eagle-import") (part "C-EUC0805"))
    )
    (comp (ref "C10")
      (value "15n")
      (footprint "eagle-import:C0805")
      (libsource (lib "eagle-import") (part "C-EUC0805"))
    )
    (comp (ref "C11")
      (value "47p")
      (footprint "eagle-import:C0805")
      (libsource (lib "eagle-import") (part "C-EUC0805"))
    )
    (comp (ref "C12")
      (value "15n")
      (footprint "eagle-import:C0805")
      (libsource (lib "eagle-import") (part "C-EUC0805"))
    )
    (comp (ref "C13")
      (value "47p")
      (footprint "eagle-import:C0805")
      (libsource (lib "eagle-import") (part "C-EUC0805"))
    )
    (comp (ref "C14")
      (value "47p")
      (footprint "eagle-import:C0805")
      (libsource (lib "eagle-import") (part "C-EUC0805"))
    )
    (comp (ref "C15")
      (value "15n")
      (footprint "eagle-import:C0805")
      (libsource (lib "eagle-import") (part "C-EUC0805"))
    )
    (comp (ref "C16")
      (value "47p")
      (footprint "eagle-import:C0805")
      (libsource (lib "eagle-import") (part "C-EUC0805"))
    )
    (comp (ref "C17")
      (value "15n")
      (footprint "eagle-import:C0805")
      (libsource (lib "eagle-import") (part "C-EUC0805"))
    )
    (comp (ref "C18")
      (value "47p")
      (footprint "eagle-import:C0805")
      (libsource (lib "eagle-import") (part "C-EUC0805"))
    )
    (comp (ref "C19")
      (value "15n")
      (footprint "eagle-import:C0805")
      (libsource (lib "eagle-import") (part "C-EUC0805"))
    )
    (comp (ref "C20")
      (value "47p")
      (footprint "eagle-import:C0805")
      (libsource (lib "eagle-import") (part "C-EUC0805"))
    )
    (comp (ref "C21")
      (value "15n")
      (footprint "eagle-import:C0805")
      (libsource (lib "eagle-import") (part "C-EUC0805"))
    )
    (comp (ref "D1")
      (value "PMLL4148")
      (footprint "eagle-import:SOD80C")
      (libsource (lib "eagle-import") (part "PMLL4148"))
    )
    (comp (ref "D2")
      (value "PMLL4148")
      (footprint "eagle-import:SOD80C")
      (libsource (lib "eagle-import") (part "PMLL4148"))
    )
    (comp (ref "D3")
      (value "PMLL4148")
      (footprint "eagle-import:SOD80C")
      (libsource (lib "eagle-import") (part "PMLL4148"))
    )
    (comp (ref "D4")
      (value "PMLL4148")
      (footprint "eagle-import:SOD80C")
      (libsource (lib "eagle-import") (part "PMLL4148"))
    )
    (comp (ref "D5")
      (value "PMLL4148")
      (footprint "eagle-import:SOD80C")
      (libsource (lib "eagle-import") (part "PMLL4148"))
    )
    (comp (ref "D6")
      (value "PMLL4148")
      (footprint "eagle-import:SOD80C")
      (libsource (lib "eagle-import") (part "PMLL4148"))
    )
    (comp (ref "D7")
      (value "PMLL4148")
      (footprint "eagle-import:SOD80C")
      (libsource (lib "eagle-import") (part "PMLL4148"))
    )
    (comp (ref "D8")
      (value "PMLL4148")
      (footprint "eagle-import:SOD80C")
      (libsource (lib "eagle-import") (part "PMLL4148"))
    )
    (comp (ref "D9")
      (value "PMLL4148")
      (footprint "eagle-import:SOD80C")
      (libsource (lib "eagle-import") (part "PMLL4148"))
    )
    (comp (ref "D10")
      (value "PMLL4148")
      (footprint "eagle-import:SOD80C")
      (libsource (lib "eagle-import") (part "PMLL4148"))
    )
    (comp (ref "D11")
      (value "PMLL4148")
      (footprint "eagle-import:SOD80C")
      (libsource (lib "eagle-import") (part "PMLL4148"))
    )
    (comp (ref "D12")
      (value "PMLL4148")
      (footprint "eagle-import:SOD80C")
      (libsource (lib "eagle-import") (part "PMLL4148"))
    )
    (comp (ref "D13")
      (value "PMLL4148")
      (footprint "eagle-import:SOD80C")
      (libsource (lib "eagle-import") (part "PMLL4148"))
    )
    (comp (ref "D14")
      (value "PMLL4148")
      (footprint "eagle-import:SOD80C")
      (libsource (lib "eagle-import") (part "PMLL4148"))
    )
    (comp (ref "D15")
      (value "PMLL4148")
      (footprint "eagle-import:SOD80C")
      (libsource (lib "eagle-import") (part "PMLL4148"))
    )
    (comp (ref "D16")
      (value "PMLL4148")
      (footprint "eagle-import:SOD80C")
      (libsource (lib "eagle-import") (part "PMLL4148"))
    )
    (comp (ref "D28")
      (value "PMLL4148")
      (footprint "eagle-import:SOD80C")
      (libsource (lib "eagle-import") (part "PMLL4148"))
    )
    (comp (ref "D29")
      (value "PMLL4148")
      (footprint "eagle-import:SOD80C")
      (libsource (lib "eagle-import") (part "PMLL4148"))
    )
    (comp (ref "D30")
      (value "PMLL4148")
      (footprint "eagle-import:SOD80C")
      (libsource (lib "eagle-import") (part "PMLL4148"))
    )
    (comp (ref "D31")
      (value "PMLL4148")
      (footprint "eagle-import:SOD80C")
      (libsource (lib "eagle-import") (part "PMLL4148"))
    )
    (comp (ref "D32")
      (value "PMLL4148")
      (footprint "eagle-import:SOD80C")
      (libsource (lib "eagle-import") (part "PMLL4148"))
    )
    (comp (ref "D33")
      (value "PMLL4148")
      (footprint "eagle-import:SOD80C")
      (libsource (lib "eagle-import") (part "PMLL4148"))
    )
    (comp (ref "D34")
      (value "PMLL4148")
      (footprint "eagle-import:SOD80C")
      (libsource (lib "eagle-import") (part "PMLL4148"))
    )
    (comp (ref "D35")
      (value "PMLL4148")
      (footprint "eagle-import:SOD80C")
      (libsource (lib "eagle-import") (part "PMLL4148"))
    )
    (comp (ref "D36")
      (value "PMLL4148")
      (footprint "eagle-import:SOD80C")
      (libsource (lib "eagle-import") (part "PMLL4148"))
    )
    (comp (ref "D37")
      (value "PMLL4148")
      (footprint "eagle-import:SOD80C")
      (libsource (lib "eagle-import") (part "PMLL4148"))
    )
    (comp (ref "D38")
      (value "PMLL4148")
      (footprint "eagle-import:SOD80C")
      (libsource (lib "eagle-import") (part "PMLL4148"))
    )
    (comp (ref "D39")
      (value "PMLL4148")
      (footprint "eagle-import:SOD80C")
      (libsource (lib "eagle-import") (part "PMLL4148"))
    )
    (comp (ref "D40")
      (value "PMLL4148")
      (footprint "eagle-import:SOD80C")
      (libsource (lib "eagle-import") (part "PMLL4148"))
    )
    (comp (ref "D41")
      (value "PMLL4148")
      (footprint "eagle-import:SOD80C")
      (libsource (lib "eagle-import") (part "PMLL4148"))
    )
    (comp (ref "D42")
      (value "PMLL4148")
      (footprint "eagle-import:SOD80C")
      (libsource (lib "eagle-import") (part "PMLL4148"))
    )
    (comp (ref "D43")
      (value "PMLL4148")
      (footprint "eagle-import:SOD80C")
      (libsource (lib "eagle-import") (part "PMLL4148"))
    )
    (comp (ref "I1+")
      (value "TPPAD1-20")
      (footprint "eagle-import:P1-20")
      (libsource (lib "eagle-import") (part "TPPAD1-20"))
    )
    (comp (ref "I1-")
      (value "TPPAD1-20")
      (footprint "eagle-import:P1-20")
      (libsource (lib "eagle-import") (part "TPPAD1-20"))
    )
    (comp (ref "I2+")
      (value "TPPAD1-20")
      (footprint "eagle-import:P1-20")
      (libsource (lib "eagle-import") (part "TPPAD1-20"))
    )
    (comp (ref "I2-")
      (value "TPPAD1-20")
      (footprint "eagle-import:P1-20")
      (libsource (lib "eagle-import") (part "TPPAD1-20"))
    )
    (comp (ref "I3+")
      (value "TPPAD1-20")
      (footprint "eagle-import:P1-20")
      (libsource (lib "eagle-import") (part "TPPAD1-20"))
    )
    (comp (ref "I3-")
      (value "TPPAD1-20")
      (footprint "eagle-import:P1-20")
      (libsource (lib "eagle-import") (part "TPPAD1-20"))
    )
    (comp (ref "IN+")
      (value "TPPAD1-20")
      (footprint "eagle-import:P1-20")
      (libsource (lib "eagle-import") (part "TPPAD1-20"))
    )
    (comp (ref "IN-")
      (value "TPPAD1-20")
      (footprint "eagle-import:P1-20")
      (libsource (lib "eagle-import") (part "TPPAD1-20"))
    )
    (comp (ref "L1")
      (value "EXCML20A")
      (footprint "eagle-import:R0805")
      (libsource (lib "eagle-import") (part "EXCELSA390805"))
    )
    (comp (ref "L3")
      (value "EXCML20A")
      (footprint "eagle-import:R0805")
      (libsource (lib "eagle-import") (part "EXCELSA390805"))
    )
    (comp (ref "L5")
      (value "EXCML20A")
      (footprint "eagle-import:R0805")
      (libsource (lib "eagle-import") (part "EXCELSA390805"))
    )
    (comp (ref "L6")
      (value "EXCML20A")
      (footprint "eagle-import:R0805")
      (libsource (lib "eagle-import") (part "EXCELSA390805"))
    )
    (comp (ref "LINE1")
      (value "TPPAD1-20")
      (footprint "eagle-import:P1-20")
      (libsource (lib "eagle-import") (part "TPPAD1-20"))
    )
    (comp (ref "LINE2")
      (value "TPPAD1-20")
      (footprint "eagle-import:P1-20")
      (libsource (lib "eagle-import") (part "TPPAD1-20"))
    )
    (comp (ref "LINE3")
      (value "TPPAD1-20")
      (footprint "eagle-import:P1-20")
      (libsource (lib "eagle-import") (part "TPPAD1-20"))
    )
    (comp (ref "NEUTRAL")
      (value "TPPAD1-20")
      (footprint "eagle-import:P1-20")
      (libsource (lib "eagle-import") (part "TPPAD1-20"))
    )
    (comp (ref "R/L7")
      (value "0")
      (footprint "eagle-import:R0805")
      (libsource (lib "eagle-import") (part "R-US_R0805"))
    )
    (comp (ref "R/L8")
      (value "0")
      (footprint "eagle-import:R0805")
      (libsource (lib "eagle-import") (part "R-US_R0805"))
    )
    (comp (ref "R/L9")
      (value "0")
      (footprint "eagle-import:R0805")
      (libsource (lib "eagle-import") (part "R-US_R0805"))
    )
    (comp (ref "R/L10")
      (value "0")
      (footprint "eagle-import:R0805")
      (libsource (lib "eagle-import") (part "R-US_R0805"))
    )
    (comp (ref "R/L11")
      (value "0")
      (footprint "eagle-import:R0805")
      (libsource (lib "eagle-import") (part "R-US_R0805"))
    )
    (comp (ref "R/L12")
      (value "0")
      (footprint "eagle-import:R0805")
      (libsource (lib "eagle-import") (part "R-US_R0805"))
    )
    (comp (ref "R/L13")
      (value "0")
      (footprint "eagle-import:R0805")
      (libsource (lib "eagle-import") (part "R-US_R0805"))
    )
    (comp (ref "R/L14")
      (value "0")
      (footprint "eagle-import:R0805")
      (libsource (lib "eagle-import") (part "R-US_R0805"))
    )
    (comp (ref "R1")
      (value "S20K275")
      (footprint "eagle-import:S20K275")
      (libsource (lib "eagle-import") (part "S20K275"))
    )
    (comp (ref "R2")
      (value "S20K275")
      (footprint "eagle-import:S20K275")
      (libsource (lib "eagle-import") (part "S20K275"))
    )
    (comp (ref "R3")
      (value "S20K275")
      (footprint "eagle-import:S20K275")
      (libsource (lib "eagle-import") (part "S20K275"))
    )
    (comp (ref "R5")
      (value "330k")
      (footprint "eagle-import:R0805")
      (libsource (lib "eagle-import") (part "RES0805"))
    )
    (comp (ref "R6")
      (value "330k")
      (footprint "eagle-import:R0805")
      (libsource (lib "eagle-import") (part "RES0805"))
    )
    (comp (ref "R7")
      (value "330k")
      (footprint "eagle-import:R0805")
      (libsource (lib "eagle-import") (part "RES0805"))
    )
    (comp (ref "R8")
      (value "330k")
      (footprint "eagle-import:R0805")
      (libsource (lib "eagle-import") (part "RES0805"))
    )
    (comp (ref "R9")
      (value "330k")
      (footprint "eagle-import:R0805")
      (libsource (lib "eagle-import") (part "RES0805"))
    )
    (comp (ref "R10")
      (value "330k")
      (footprint "eagle-import:R0805")
      (libsource (lib "eagle-import") (part "RES0805"))
    )
    (comp (ref "R11")
      (value "330k")
      (footprint "eagle-import:R0805")
      (libsource (lib "eagle-import") (part "RES0805"))
    )
    (comp (ref "R12")
      (value "330k")
      (footprint "eagle-import:R0805")
      (libsource (lib "eagle-import") (part "RES0805"))
    )
    (comp (ref "R13")
      (value "330k")
      (footprint "eagle-import:R0805")
      (libsource (lib "eagle-import") (part "RES0805"))
    )
    (comp (ref "R14")
      (value "1k")
      (footprint "eagle-import:R0805")
      (libsource (lib "eagle-import") (part "RES0805"))
    )
    (comp (ref "R15")
      (value "2.37K")
      (footprint "eagle-import:R0805")
      (libsource (lib "eagle-import") (part "RES0805"))
    )
    (comp (ref "R16")
      (value "1k")
      (footprint "eagle-import:R0805")
      (libsource (lib "eagle-import") (part "RES0805"))
    )
    (comp (ref "R17")
      (value "2.37K")
      (footprint "eagle-import:R0805")
      (libsource (lib "eagle-import") (part "RES0805"))
    )
    (comp (ref "R18")
      (value "1k")
      (footprint "eagle-import:R0805")
      (libsource (lib "eagle-import") (part "RES0805"))
    )
    (comp (ref "R19")
      (value "2.37K")
      (footprint "eagle-import:R0805")
      (libsource (lib "eagle-import") (part "RES0805"))
    )
    (comp (ref "R20")
      (value "12.4")
      (footprint "eagle-import:R0805")
      (libsource (lib "eagle-import") (part "resistor_R-US_R0805"))
    )
    (comp (ref "R21")
      (value "12.4")
      (footprint "eagle-import:R0805")
      (libsource (lib "eagle-import") (part "resistor_R-US_R0805"))
    )
    (comp (ref "R22")
      (value "12.4")
      (footprint "eagle-import:R0805")
      (libsource (lib "eagle-import") (part "resistor_R-US_R0805"))
    )
    (comp (ref "R23")
      (value "12.4")
      (footprint "eagle-import:R0805")
      (libsource (lib "eagle-import") (part "resistor_R-US_R0805"))
    )
    (comp (ref "R24")
      (value "1k")
      (footprint "eagle-import:R0805")
      (libsource (lib "eagle-import") (part "RES0805"))
    )
    (comp (ref "R25")
      (value "1k")
      (footprint "eagle-import:R0805")
      (libsource (lib "eagle-import") (part "RES0805"))
    )
    (comp (ref "R26")
      (value "1k")
      (footprint "eagle-import:R0805")
      (libsource (lib "eagle-import") (part "RES0805"))
    )
    (comp (ref "R27")
      (value "1k")
      (footprint "eagle-import:R0805")
      (libsource (lib "eagle-import") (part "RES0805"))
    )
    (comp (ref "R28")
      (value "1k")
      (footprint "eagle-import:R0805")
      (libsource (lib "eagle-import") (part "RES0805"))
    )
    (comp (ref "R29")
      (value "1k")
      (footprint "eagle-import:R0805")
      (libsource (lib "eagle-import") (part "RES0805"))
    )
    (comp (ref "R30")
      (value "1k")
      (footprint "eagle-import:R0805")
      (libsource (lib "eagle-import") (part "RES0805"))
    )
    (comp (ref "R31")
      (value "1k")
      (footprint "eagle-import:R0805")
      (libsource (lib "eagle-import") (part "RES0805"))
    )
    (comp (ref "R32")
      (value "1k")
      (footprint "eagle-import:R0805")
      (libsource (lib "eagle-import") (part "RES0805"))
    )
    (comp (ref "R33")
      (value "1k")
      (footprint "eagle-import:R0805")
      (libsource (lib "eagle-import") (part "RES0805"))
    )
    (comp (ref "R34")
      (value "1k")
      (footprint "eagle-import:R0805")
      (libsource (lib "eagle-import") (part "RES0805"))
    )
    (comp (ref "TVS1")
      (value "SMAJ5.0CA")
      (footprint "eagle-import:DO214AC")
      (libsource (lib "eagle-import") (part "SMAJ5.0CA"))
    )
    (comp (ref "TVS2")
      (value "SMAJ5.0CA")
      (footprint "eagle-import:DO214AC")
      (libsource (lib "eagle-import") (part "SMAJ5.0CA"))
    )
    (comp (ref "TVS3")
      (value "SMAJ5.0CA")
      (footprint "eagle-import:DO214AC")
      (libsource (lib "eagle-import") (part "SMAJ5.0CA"))
    )
    (comp (ref "TVS4")
      (value "SMAJ5.0CA")
      (footprint "eagle-import:DO214AC")
      (libsource (lib "eagle-import") (part "SMAJ5.0CA"))
    )
  )
  (nets
    (net (code "1") (name "ACLK") (class "Default")
      (node (ref "MSP430F67791") (pin "9") (pinfunction "P1.2/ACLK/A2_9") (pintype "bidirectional"))
      (node (ref "SV2") (pin "3") (pinfunction "3_3") (pintype "passive"))
    )
    (net (code "2") (name "ACT") (class "Default")
      (node (ref "JP12") (pin "1") (pinfunction "1_1") (pintype "passive"))
      (node (ref "LED_ACT") (pin "K") (pinfunction "C_K") (pintype "passive"))
      (node (ref "MSP430F67791") (pin "29") (pinfunction "P5.3/COM7_29") (pintype "bidirectional"))
      (node (ref "R72") (pin "1") (pinfunction "1_1") (pintype "passive"))
    )
    (net (code "3") (name "AGND") (class "Default")
      (node (ref "C1") (pin "2") (pinfunction "2_2") (pintype "passive"))
      (node (ref "C11") (pin "2") (pinfunction "2_2") (pintype "passive"))
      (node (ref "C13") (pin "2") (pinfunction "2_2") (pintype "passive"))
      (node (ref "C14") (pin "2") (pinfunction "2_2") (pintype "passive"))
      (node (ref "C16") (pin "2") (pinfunction "2_2") (pintype "passive"))
      (node (ref "C18") (pin "2") (pinfunction "2_2") (pintype "passive"))
      (node (ref "C2") (pin "2") (pinfunction "2_2") (pintype "passive"))
      (node (ref "C20") (pin "2") (pinfunction "2_2") (pintype "passive"))
      (node (ref "C22") (pin "2") (pinfunction "2_2") (pintype "passive"))
      (node (ref "C23") (pin "2") (pinfunction "2_2") (pintype "passive"))
      (node (ref "C28") (pin "2") (pinfunction "2_2") (pintype "passive"))
      (node (ref "C29") (pin "2") (pinfunction "2_2") (pintype "passive"))
      (node (ref "C3") (pin "2") (pinfunction "2_2") (pintype "passive"))
      (node (ref "C30") (pin "2") (pinfunction "2_2") (pintype "passive"))
      (node (ref "C31") (pin "2") (pinfunction "2_2") (pintype "passive"))
      (node (ref "C32") (pin "2") (pinfunction "2_2") (pintype "passive"))
      (node (ref "C4") (pin "2") (pinfunction "2_2") (pintype "passive"))
      (node (ref "C5") (pin "2") (pinfunction "2_2") (pintype "passive"))
      (node (ref "C6") (pin "2") (pinfunction "2_2") (pintype "passive"))
      (node (ref "C7") (pin "2") (pinfunction "2_2") (pintype "passive"))
      (node (ref "C9") (pin "2") (pinfunction "2_2") (pintype "passive"))
      (node (ref "D29") (pin "A") (pinfunction "A_A") (pintype "passive"))
      (node (ref "D31") (pin "A") (pinfunction "A_A") (pintype "passive"))
      (node (ref "D33") (pin "A") (pinfunction "A_A") (pintype "passive"))
      (node (ref "D35") (pin "A") (pinfunction "A_A") (pintype "passive"))
      (node (ref "D37") (pin "A") (pinfunction "A_A") (pintype "passive"))
      (node (ref "D39") (pin "A") (pinfunction "A_A") (pintype "passive"))
      (node (ref "D41") (pin "A") (pinfunction "A_A") (pintype "passive"))
      (node (ref "D43") (pin "A") (pinfunction "A_A") (pintype "passive"))
      (node (ref "L6") (pin "2") (pinfunction "2_2") (pintype "passive"))
      (node (ref "MSP430F67791") (pin "112") (pinfunction "AVSS2_112") (pintype "bidirectional"))
      (node (ref "MSP430F67791") (pin "120") (pinfunction "AVSS1_120") (pintype "bidirectional"))
      (node (ref "R/L10") (pin "1") (pinfunction "1_1") (pintype "passive"))
      (node (ref "R/L12") (pin "1") (pinfunction "1_1") (pintype "passive"))
      (node (ref "R/L14") (pin "1") (pinfunction "1_1") (pintype "passive"))
      (node (ref "R/L8") (pin "1") (pinfunction "1_1") (pintype "passive"))
      (node (ref "R100") (pin "2") (pinfunction "2_2") (pintype "passive"))
      (node (ref "R101") (pin "2") (pinfunction "2_2") (pintype "passive"))
      (node (ref "R102") (pin "2") (pinfunction "2_2") (pintype "passive"))
      (node (ref "R103") (pin "2") (pinfunction "2_2") (pintype "passive"))
      (node (ref "R15") (pin "2") (pinfunction "2_2") (pintype "passive"))
      (node (ref "R17") (pin "2") (pinfunction "2_2") (pintype "passive"))
      (node (ref "R19") (pin "2") (pinfunction "2_2") (pintype "passive"))
      (node (ref "R20") (pin "1") (pinfunction "1_1") (pintype "passive"))
      (node (ref "R21") (pin "1") (pinfunction "1_1") (pintype "passive"))
      (node (ref "R22") (pin "1") (pinfunction "1_1") (pintype "passive"))
      (node (ref "R23") (pin "1") (pinfunction "1_1") (pintype "passive"))
      (node (ref "R25") (pin "1") (pinfunction "1_1") (pintype "passive"))
      (node (ref "R27") (pin "1") (pinfunction "1_1") (pintype "passive"))
      (node (ref "R29") (pin "1") (pinfunction "1_1") (pintype "passive"))
      (node (ref "R31") (pin "1") (pinfunction "1_1") (pintype "passive"))
      (node (ref "R32") (pin "2") (pinfunction "2_2") (pintype "passive"))
      (node (ref "R33") (pin "2") (pinfunction "2_2") (pintype "passive"))
      (node (ref "R34") (pin "2") (pinfunction "2_2") (pintype "passive"))
      (node (ref "R4") (pin "2") (pinfunction "2_2") (pintype "passive"))
      (node (ref "R99") (pin "2") (pinfunction "2_2") (pintype "passive"))
    )
    (net (code "4") (name "AUXVCC1") (class "Default")
      (node (ref "C26") (pin "1") (pinfunction "1_1") (pintype "passive"))
      (node (ref "C27") (pin "1") (pinfunction "1_1") (pintype "passive"))
      (node (ref "MSP430F67791") (pin "124") (pinfunction "AUXVCC1_124") (pintype "bidirectional"))
      (node (ref "SV1") (pin "3") (pinfunction "3_3") (pintype "passive"))
    )
    (net (code "5") (name "AUXVCC2") (class "Default")
      (node (ref "C24") (pin "1") (pinfunction "1_1") (pintype "passive"))
      (node (ref "C25") (pin "1") (pinfunction "1_1") (pintype "passive"))
      (node (ref "MSP430F67791") (pin "123") (pinfunction "AUXVCC2_123") (pintype "bidirectional"))
      (node (ref "SV1") (pin "1") (pinfunction "1_1") (pintype "passive"))
    )
    (net (code "6") (name "AUXVCC3") (class "Default")
      (node (ref "AUXVCC3") (pin "2") (pinfunction "2_2") (pintype "passive"))
      (node (ref "C43") (pin "1") (pinfunction "1_1") (pintype "passive"))
      (node (ref "C44") (pin "1") (pinfunction "1_1") (pintype "passive"))
      (node (ref "MSP430F67791") (pin "3") (pinfunction "AUXVCC3_3") (pintype "bidirectional"))
    )
    (net (code "7") (name "AVCC") (class "Default")
      (node (ref "C29") (pin "1") (pinfunction "1_1") (pintype "passive"))
      (node (ref "C31") (pin "1") (pinfunction "1_1") (pintype "passive"))
      (node (ref "D28") (pin "C") (pinfunction "C_C") (pintype "passive"))
      (node (ref "D30") (pin "C") (pinfunction "C_C") (pintype "passive"))
      (node (ref "D32") (pin "C") (pinfunction "C_C") (pintype "passive"))
      (node (ref "D34") (pin "C") (pinfunction "C_C") (pintype "passive"))
      (node (ref "D36") (pin "C") (pinfunction "C_C") (pintype "passive"))
      (node (ref "D38") (pin "C") (pinfunction "C_C") (pintype "passive"))
      (node (ref "D40") (pin "C") (pinfunction "C_C") (pintype "passive"))
      (node (ref "D42") (pin "C") (pinfunction "C_C") (pintype "passive"))
      (node (ref "MSP430F67791") (pin "121") (pinfunction "AVCC_121") (pintype "bidirectional"))
      (node (ref "R36") (pin "2") (pinfunction "2_2") (pintype "passive"))
    )
    (net (code "8") (name "BTN1") (class "Default")
      (node (ref "BTN4") (pin "2") (pinfunction "S_2") (pintype "passive"))
      (node (ref "MSP430F67791") (pin "11") (pinfunction "P1.0/TA1.1/VEREF-/A0_11") (pintype "bidirectional"))
      (node (ref "R53") (pin "2") (pinfunction "2_2") (pintype "passive"))
    )
    (net (code "9") (name "BTN2") (class "Default")
      (node (ref "BTN2") (pin "2") (pinfunction "S_2") (pintype "passive"))
      (node (ref "MSP430F67791") (pin "10") (pinfunction "P1.1/TA2.1/VEREF+/A1_10") (pintype "bidirectional"))
      (node (ref "R50") (pin "2") (pinfunction "2_2") (pintype "passive"))
    )
    (net (code "10") (name "BTN3") (class "Default")
      (node (ref "BTN1") (pin "2") (pinfunction "S_2") (pintype "passive"))
      (node (ref "MSP430F67791") (pin "4") (pinfunction "RTCCAP1_4") (pintype "bidirectional"))
      (node (ref "R49") (pin "2") (pinfunction "2_2") (pintype "passive"))
    )
    (net (code "11") (name "BTN4") (class "Default")
      (node (ref "BTN3") (pin "2") (pinfunction "S_2") (pintype "passive"))
      (node (ref "MSP430F67791") (pin "5") (pinfunction "RTCCAP0_5") (pintype "bidirectional"))
      (node (ref "R52") (pin "2") (pinfunction "2_2") (pintype "passive"))
    )
    (net (code "12") (name "CBOUT") (class "Default")
      (node (ref "JP13") (pin "1") (pinfunction "1_1") (pintype "passive"))
      (node (ref "MSP430F67791") (pin "91") (pinfunction "CBOUT/P11.4_91") (pintype "bidirectional"))
    )
    (net (code "13") (name "COM0") (class "Default")
      (node (ref "LCD1") (pin "COM0") (pinfunction "COM0_COM0") (pintype "bidirectional"))
      (node (ref "MSP430F67791") (pin "22") (pinfunction "COM0_22") (pintype "bidirectional"))
    )
    (net (code "14") (name "COM1") (class "Default")
      (node (ref "LCD1") (pin "COM1") (pinfunction "COM1_COM1") (pintype "bidirectional"))
      (node (ref "MSP430F67791") (pin "23") (pinfunction "COM1_23") (pintype "bidirectional"))
    )
    (net (code "15") (name "COM2") (class "Default")
      (node (ref "LCD1") (pin "COM2") (pinfunction "COM2_COM2") (pintype "bidirectional"))
      (node (ref "MSP430F67791") (pin "24") (pinfunction "P1.6/COM2_24") (pintype "bidirectional"))
    )
    (net (code "16") (name "COM3") (class "Default")
      (node (ref "LCD1") (pin "COM3") (pinfunction "COM3_COM3") (pintype "bidirectional"))
      (node (ref "MSP430F67791") (pin "25") (pinfunction "P1.7/COM3_25") (pintype "bidirectional"))
    )
    (net (code "17") (name "CUR1+") (class "Default")
      (node (ref "D11") (pin "C") (pinfunction "C_C") (pintype "passive"))
      (node (ref "D3") (pin "A") (pinfunction "A_A") (pintype "passive"))
      (node (ref "I1+") (pin "TP") (pinfunction "TP_TP") (pintype "input"))
      (node (ref "R/L9") (pin "2") (pinfunction "2_2") (pintype "passive"))
      (node (ref "TVS2") (pin "C") (pinfunction "K_C") (pintype "passive"))
    )
    (net (code "18") (name "CUR1-") (class "Default")
      (node (ref "D12") (pin "C") (pinfunction "C_C") (pintype "passive"))
      (node (ref "D4") (pin "A") (pinfunction "A_A") (pintype "passive"))
      (node (ref "I1-") (pin "TP") (pinfunction "TP_TP") (pintype "input"))
      (node (ref "R/L10") (pin "2") (pinfunction "2_2") (pintype "passive"))
      (node (ref "TVS2") (pin "A") (pinfunction "A_A") (pintype "passive"))
    )
    (net (code "19") (name "CUR2+") (class "Default")
      (node (ref "D13") (pin "C") (pinfunction "C_C") (pintype "passive"))
      (node (ref "D5") (pin "A") (pinfunction "A_A") (pintype "passive"))
      (node (ref "I2+") (pin "TP") (pinfunction "TP_TP") (pintype "input"))
      (node (ref "R/L11") (pin "2") (pinfunction "2_2") (pintype "passive"))
      (node (ref "TVS3") (pin "C") (pinfunction "K_C") (pintype "passive"))
    )
    (net (code "20") (name "CUR2-") (class "Default")
      (node (ref "D14") (pin "C") (pinfunction "C_C") (pintype "passive"))
      (node (ref "D6") (pin "A") (pinfunction "A_A") (pintype "passive"))
      (node (ref "I2-") (pin "TP") (pinfunction "TP_TP") (pintype "input"))
      (node (ref "R/L12") (pin "2") (pinfunction "2_2") (pintype "passive"))
      (node (ref "TVS3") (pin "A") (pinfunction "A_A") (pintype "passive"))
    )
    (net (code "21") (name "CUR3+") (class "Default")
      (node (ref "D15") (pin "C") (pinfunction "C_C") (pintype "passive"))
      (node (ref "D7") (pin "A") (pinfunction "A_A") (pintype "passive"))
      (node (ref "I3+") (pin "TP") (pinfunction "TP_TP") (pintype "input"))
      (node (ref "R/L13") (pin "2") (pinfunction "2_2") (pintype "passive"))
      (node (ref "TVS4") (pin "C") (pinfunction "K_C") (pintype "passive"))
    )
    (net (code "22") (name "CUR3-") (class "Default")
      (node (ref "D16") (pin "C") (pinfunction "C_C") (pintype "passive"))
      (node (ref "D8") (pin "A") (pinfunction "A_A") (pintype "passive"))
      (node (ref "I3-") (pin "TP") (pinfunction "TP_TP") (pintype "input"))
      (node (ref "R/L14") (pin "2") (pinfunction "2_2") (pintype "passive"))
      (node (ref "TVS4") (pin "A") (pinfunction "A_A") (pintype "passive"))
    )
    (net (code "23") (name "CURN+") (class "Default")
      (node (ref "D1") (pin "A") (pinfunction "A_A") (pintype "passive"))
      (node (ref "D9") (pin "C") (pinfunction "C_C") (pintype "passive"))
      (node (ref "IN+") (pin "TP") (pinfunction "TP_TP") (pintype "input"))
      (node (ref "R/L7") (pin "2") (pinfunction "2_2") (pintype "passive"))
      (node (ref "TVS1") (pin "C") (pinfunction "K_C") (pintype "passive"))
    )
    (net (code "24") (name "CURN-") (class "Default")
      (node (ref "D10") (pin "C") (pinfunction "C_C") (pintype "passive"))
      (node (ref "D2") (pin "A") (pinfunction "A_A") (pintype "passive"))
      (node (ref "IN-") (pin "TP") (pinfunction "TP_TP") (pintype "input"))
      (node (ref "R/L8") (pin "2") (pinfunction "2_2") (pintype "passive"))
      (node (ref "TVS1") (pin "A") (pinfunction "A_A") (pintype "passive"))
    )
    (net (code "25") (name "DB9_+12V") (class "Default")
      (node (ref "C54") (pin "2") (pinfunction "2_2") (pintype "passive"))
      (node (ref "C55") (pin "+") (pinfunction "+_+") (pintype "passive"))
      (node (ref "D25") (pin "1") (pinfunction "C_1") (pintype "passive"))
      (node (ref "D26") (pin "1") (pinfunction "C_1") (pintype "passive"))
      (node (ref "Q1") (pin "E") (pinfunction "E_E") (pintype "passive"))
      (node (ref "R63") (pin "2") (pinfunction "2_2") (pintype "passive"))
      (node (ref "U1") (pin "8") (pinfunction "VCC_8") (pintype "passive"))
    )
    (net (code "26") (name "DB9_-12V") (class "Default")
      (node (ref "C54") (pin "1") (pinfunction "1_1") (pintype "passive"))
      (node (ref "C56") (pin "-") (pinfunction "-_-") (pintype "passive"))
      (node (ref "D24") (pin "2") (pinfunction "A_2") (pintype "passive"))
      (node (ref "R66") (pin "2") (pinfunction "2_2") (pintype "passive"))
      (node (ref "R67") (pin "1") (pinfunction "1_1") (pintype "passive"))
      (node (ref "U1") (pin "5") (pinfunction "GND_5") (pintype "passive"))
    )
    (net (code "27") (name "DB9_GND") (class "Default")
      (node (ref "C55") (pin "-") (pinfunction "-_-") (pintype "passive"))
      (node (ref "C56") (pin "+") (pinfunction "+_+") (pintype "passive"))
      (node (ref "D27") (pin "2") (pinfunction "A_2") (pintype "passive"))
      (node (ref "RS-232") (pin "5") (pinfunction "5_5") (pintype "passive"))
      (node (ref "RS-232") (pin "G1") (pinfunction "G1_G1") (pintype "passive"))
      (node (ref "RS-232") (pin "G2") (pinfunction "G2_G2") (pintype "passive"))
      (node (ref "U2") (pin "3") (pinfunction "C_3") (pintype "passive"))
    )
    (net (code "28") (name "DGND") (class "Default")
      (node (ref "BTN1") (pin "1") (pinfunction "P_1") (pintype "passive"))
      (node (ref "BTN2") (pin "1") (pinfunction "P_1") (pintype "passive"))
      (node (ref "BTN3") (pin "1") (pinfunction "P_1") (pintype "passive"))
      (node (ref "BTN4") (pin "1") (pinfunction "P_1") (pintype "passive"))
      (node (ref "C101") (pin "-") (pinfunction "-_-") (pintype "passive"))
      (node (ref "C24") (pin "2") (pinfunction "2_2") (pintype "passive"))
      (node (ref "C25") (pin "2") (pinfunction "2_2") (pintype "passive"))
      (node (ref "C26") (pin "2") (pinfunction "2_2") (pintype "passive"))
      (node (ref "C27") (pin "2") (pinfunction "2_2") (pintype "passive"))
      (node (ref "C33") (pin "2") (pinfunction "2_2") (pintype "passive"))
      (node (ref "C34") (pin "2") (pinfunction "2_2") (pintype "passive"))
      (node (ref "C35") (pin "2") (pinfunction "2_2") (pintype "passive"))
      (node (ref "C36") (pin "2") (pinfunction "2_2") (pintype "passive"))
      (node (ref "C37") (pin "2") (pinfunction "2_2") (pintype "passive"))
      (node (ref "C38") (pin "2") (pinfunction "2_2") (pintype "passive"))
      (node (ref "C40") (pin "2") (pinfunction "2_2") (pintype "passive"))
      (node (ref "C41") (pin "1") (pinfunction "1_1") (pintype "passive"))
      (node (ref "C42") (pin "2") (pinfunction "2_2") (pintype "passive"))
      (node (ref "C43") (pin "2") (pinfunction "2_2") (pintype "passive"))
      (node (ref "C44") (pin "2") (pinfunction "2_2") (pintype "passive"))
      (node (ref "C49") (pin "2") (pinfunction "2_2") (pintype "passive"))
      (node (ref "C51") (pin "2") (pinfunction "2_2") (pintype "passive"))
      (node (ref "C52") (pin "2") (pinfunction "2_2") (pintype "passive"))
      (node (ref "C53") (pin "1") (pinfunction "1_1") (pintype "passive"))
      (node (ref "C57") (pin "2") (pinfunction "2_2") (pintype "passive"))
      (node (ref "C58") (pin "-") (pinfunction "-_-") (pintype "passive"))
      (node (ref "C59") (pin "1") (pinfunction "1_1") (pintype "passive"))
      (node (ref "DGND") (pin "1") (pinfunction "1_1") (pintype "passive"))
      (node (ref "DGND") (pin "2") (pinfunction "2_2") (pintype "passive"))
      (node (ref "DGND") (pin "3") (pinfunction "3_3") (pintype "passive"))
      (node (ref "DGND") (pin "4") (pinfunction "4_4") (pintype "passive"))
      (node (ref "EZ-RF") (pin "5") (pinfunction "5_5") (pintype "passive"))
      (node (ref "HD1") (pin "1") (pinfunction "1_1") (pintype "passive"))
      (node (ref "IC1") (pin "1") (pinfunction "A0_1") (pintype "input"))
      (node (ref "IC1") (pin "2") (pinfunction "A1_2") (pintype "input"))
      (node (ref "IC1") (pin "3") (pinfunction "A2_3") (pintype "input"))
      (node (ref "IC1") (pin "4") (pinfunction "GND_4") (pintype "power_in"))
      (node (ref "IC1") (pin "7") (pinfunction "WP_7") (pintype "input"))
      (node (ref "IRDA") (pin "P$6") (pinfunction "GND_P$6") (pintype "bidirectional"))
      (node (ref "JP11") (pin "2") (pinfunction "2_2") (pintype "passive"))
      (node (ref "JP12") (pin "2") (pinfunction "2_2") (pintype "passive"))
      (node (ref "JTAG") (pin "9") (pinfunction "9_9") (pintype "passive"))
      (node (ref "MSP430F67791") (pin "127") (pinfunction "DVSS1_127") (pintype "bidirectional"))
      (node (ref "MSP430F67791") (pin "33") (pinfunction "P5.6/SD1DIO/R03_33") (pintype "bidirectional"))
      (node (ref "MSP430F67791") (pin "70") (pinfunction "DVSS2_70") (pintype "bidirectional"))
      (node (ref "Q2") (pin "C") (pinfunction "C_C") (pintype "passive"))
      (node (ref "R100") (pin "1") (pinfunction "1_1") (pintype "passive"))
      (node (ref "R101") (pin "1") (pinfunction "1_1") (pintype "passive"))
      (node (ref "R102") (pin "1") (pinfunction "1_1") (pintype "passive"))
      (node (ref "R103") (pin "1") (pinfunction "1_1") (pintype "passive"))
      (node (ref "R39") (pin "1") (pinfunction "1_1") (pintype "passive"))
      (node (ref "R4") (pin "1") (pinfunction "1_1") (pintype "passive"))
      (node (ref "R44") (pin "1") (pinfunction "1_1") (pintype "passive"))
      (node (ref "R46") (pin "1") (pinfunction "1_1") (pintype "passive"))
      (node (ref "R73") (pin "2") (pinfunction "2_2") (pintype "passive"))
      (node (ref "R77") (pin "2") (pinfunction "2_2") (pintype "passive"))
      (node (ref "R99") (pin "1") (pinfunction "1_1") (pintype "passive"))
      (node (ref "RESET") (pin "2") (pinfunction "S_2") (pintype "passive"))
      (node (ref "RF1") (pin "2") (pinfunction "2_2") (pintype "passive"))
      (node (ref "RF2") (pin "1") (pinfunction "1_1") (pintype "passive"))
      (node (ref "RF2") (pin "19") (pinfunction "19_19") (pintype "passive"))
      (node (ref "SV1") (pin "2") (pinfunction "2_2") (pintype "passive"))
      (node (ref "SV1") (pin "4") (pinfunction "4_4") (pintype "passive"))
      (node (ref "SV2") (pin "1") (pinfunction "1_1") (pintype "passive"))
      (node (ref "U$1") (pin "VO-") (pinfunction "VO-_VO-") (pintype "bidirectional"))
      (node (ref "U2") (pin "5") (pinfunction "GND_5") (pintype "passive"))
      (node (ref "XT1") (pin "P3") (pinfunction "3_P3") (pintype "bidirectional"))
      (node (ref "ZD3") (pin "A") (pinfunction "A_A") (pintype "passive"))
    )
    (net (code "29") (name "DRESET") (class "Default")
      (node (ref "JP5") (pin "2") (pinfunction "2_2") (pintype "passive"))
      (node (ref "MSP430F67791") (pin "102") (pinfunction "SBWTDIO/NMI/RST_102") (pintype "bidirectional"))
    )
    (net (code "30") (name "DTCK") (class "Default")
      (node (ref "JP6") (pin "2") (pinfunction "2_2") (pintype "passive"))
      (node (ref "MSP430F67791") (pin "101") (pinfunction "TCK/PJ.3_101") (pintype "bidirectional"))
    )
    (net (code "31") (name "DTDI") (class "Default")
      (node (ref "JP8") (pin "2") (pinfunction "2_2") (pintype "passive"))
      (node (ref "MSP430F67791") (pin "99") (pinfunction "TCLK/TDI/PJ.1_99") (pintype "bidirectional"))
    )
    (net (code "32") (name "DTDO") (class "Default")
      (node (ref "JP9") (pin "2") (pinfunction "2_2") (pintype "passive"))
      (node (ref "MSP430F67791") (pin "98") (pinfunction "TDO/PJ.0_98") (pintype "bidirectional"))
    )
    (net (code "33") (name "DTMS") (class "Default")
      (node (ref "JP7") (pin "2") (pinfunction "2_2") (pintype "passive"))
      (node (ref "MSP430F67791") (pin "100") (pinfunction "TMS/PJ.2_100") (pintype "bidirectional"))
    )
    (net (code "34") (name "DVCC") (class "Default")
      (node (ref "C33") (pin "1") (pinfunction "1_1") (pintype "passive"))
      (node (ref "C35") (pin "1") (pinfunction "1_1") (pintype "passive"))
      (node (ref "C41") (pin "2") (pinfunction "2_2") (pintype "passive"))
      (node (ref "C51") (pin "1") (pinfunction "1_1") (pintype "passive"))
      (node (ref "C57") (pin "1") (pinfunction "1_1") (pintype "passive"))
      (node (ref "C58") (pin "+") (pinfunction "+_+") (pintype "passive"))
      (node (ref "C59") (pin "2") (pinfunction "2_2") (pintype "passive"))
      (node (ref "DVCC") (pin "1") (pinfunction "1_1") (pintype "passive"))
      (node (ref "DVCC") (pin "2") (pinfunction "2_2") (pintype "passive"))
      (node (ref "DVCC") (pin "3") (pinfunction "3_3") (pintype "passive"))
      (node (ref "DVCC") (pin "4") (pinfunction "4_4") (pintype "passive"))
      (node (ref "EZ-RF") (pin "2") (pinfunction "2_2") (pintype "passive"))
      (node (ref "IC1") (pin "8") (pinfunction "VCC_8") (pintype "power_in"))
      (node (ref "IRDA") (pin "P$1") (pinfunction "VCC2_P$1") (pintype "bidirectional"))
      (node (ref "JP10") (pin "2") (pinfunction "2_2") (pintype "passive"))
      (node (ref "JP3") (pin "2") (pinfunction "2_2") (pintype "passive"))
      (node (ref "MSP430F67791") (pin "126") (pinfunction "DVCC_126") (pintype "bidirectional"))
      (node (ref "OPTO1") (pin "1") (pinfunction "A_1") (pintype "passive"))
      (node (ref "OPTO2") (pin "1") (pinfunction "A_1") (pintype "passive"))
      (node (ref "R36") (pin "1") (pinfunction "1_1") (pintype "passive"))
      (node (ref "R40") (pin "2") (pinfunction "2_2") (pintype "passive"))
      (node (ref "R41") (pin "2") (pinfunction "2_2") (pintype "passive"))
      (node (ref "R47") (pin "1") (pinfunction "1_1") (pintype "passive"))
      (node (ref "R49") (pin "1") (pinfunction "1_1") (pintype "passive"))
      (node (ref "R50") (pin "1") (pinfunction "1_1") (pintype "passive"))
      (node (ref "R51") (pin "1") (pinfunction "1_1") (pintype "passive"))
      (node (ref "R52") (pin "1") (pinfunction "1_1") (pintype "passive"))
      (node (ref "R53") (pin "1") (pinfunction "1_1") (pintype "passive"))
      (node (ref "R54") (pin "1") (pinfunction "1_1") (pintype "passive"))
      (node (ref "R55") (pin "1") (pinfunction "1_1") (pintype "passive"))
      (node (ref "R56") (pin "1") (pinfunction "1_1") (pintype "passive"))
      (node (ref "R57") (pin "1") (pinfunction "1_1") (pintype "passive"))
      (node (ref "R58") (pin "1") (pinfunction "1_1") (pintype "passive"))
      (node (ref "R59") (pin "1") (pinfunction "1_1") (pintype "passive"))
      (node (ref "R60") (pin "1") (pinfunction "1_1") (pintype "passive"))
      (node (ref "R61") (pin "1") (pinfunction "1_1") (pintype "passive"))
      (node (ref "R65") (pin "1") (pinfunction "1_1") (pintype "passive"))
      (node (ref "R70") (pin "2") (pinfunction "2_2") (pintype "passive"))
      (node (ref "R71") (pin "1") (pinfunction "1_1") (pintype "passive"))
      (node (ref "R79") (pin "1") (pinfunction "1_1") (pintype "passive"))
      (node (ref "RF1") (pin "9") (pinfunction "9_9") (pintype "passive"))
      (node (ref "U2") (pin "8") (pinfunction "VCC_8") (pintype "passive"))
    )
    (net (code "35") (name "DVSYS_VDSYS") (class "Default")
      (node (ref "AUXVCC3") (pin "3") (pinfunction "3_3") (pintype "passive"))
      (node (ref "C34") (pin "1") (pinfunction "1_1") (pintype "passive"))
      (node (ref "C36") (pin "1") (pinfunction "1_1") (pintype "passive"))
      (node (ref "MSP430F67791") (pin "125") (pinfunction "VDSYS_125") (pintype "bidirectional"))
      (node (ref "MSP430F67791") (pin "69") (pinfunction "DVSYS_69") (pintype "bidirectional"))
    )
    (net (code "36") (name "EXT") (class "Default")
      (node (ref "JP10") (pin "3") (pinfunction "3_3") (pintype "passive"))
      (node (ref "JTAG") (pin "4") (pinfunction "4_4") (pintype "passive"))
    )
    (net (code "37") (name "EZ-RF_RXD") (class "Default")
      (node (ref "EZ-RF") (pin "6") (pinfunction "6_6") (pintype "passive"))
      (node (ref "MSP430F67791") (pin "36") (pinfunction "P3.6/PM_UCA2RXD/PM_UCA2SOMI_36") (pintype "bidirectional"))
    )
    (net (code "38") (name "EZ-RF_TXD") (class "Default")
      (node (ref "EZ-RF") (pin "1") (pinfunction "1_1") (pintype "passive"))
      (node (ref "MSP430F67791") (pin "37") (pinfunction "P3.7/PM_UCA2TXD/PM_UCA2SIMO_37") (pintype "bidirectional"))
    )
    (net (code "39") (name "I1+") (class "Default")
      (node (ref "C16") (pin "1") (pinfunction "1_1") (pintype "passive"))
      (node (ref "C17") (pin "1") (pinfunction "1_1") (pintype "passive"))
      (node (ref "MSP430F67791") (pin "114") (pinfunction "SD4P0_114") (pintype "bidirectional"))
      (node (ref "R26") (pin "2") (pinfunction "2_2") (pintype "passive"))
    )
    (net (code "40") (name "I1-") (class "Default")
      (node (ref "C17") (pin "2") (pinfunction "2_2") (pintype "passive"))
      (node (ref "C5") (pin "1") (pinfunction "1_1") (pintype "passive"))
      (node (ref "MSP430F67791") (pin "115") (pinfunction "SD4N0_115") (pintype "bidirectional"))
      (node (ref "R27") (pin "2") (pinfunction "2_2") (pintype "passive"))
    )
    (net (code "41") (name "I2+") (class "Default")
      (node (ref "C18") (pin "1") (pinfunction "1_1") (pintype "passive"))
      (node (ref "C19") (pin "1") (pinfunction "1_1") (pintype "passive"))
      (node (ref "MSP430F67791") (pin "116") (pinfunction "SD5P0_116") (pintype "bidirectional"))
      (node (ref "R28") (pin "2") (pinfunction "2_2") (pintype "passive"))
    )
    (net (code "42") (name "I2-") (class "Default")
      (node (ref "C19") (pin "2") (pinfunction "2_2") (pintype "passive"))
      (node (ref "C6") (pin "1") (pinfunction "1_1") (pintype "passive"))
      (node (ref "MSP430F67791") (pin "117") (pinfunction "SD5N0_117") (pintype "bidirectional"))
      (node (ref "R29") (pin "2") (pinfunction "2_2") (pintype "passive"))
    )
    (net (code "43") (name "I3+") (class "Default")
      (node (ref "C20") (pin "1") (pinfunction "1_1") (pintype "passive"))
      (node (ref "C21") (pin "1") (pinfunction "1_1") (pintype "passive"))
      (node (ref "MSP430F67791") (pin "118") (pinfunction "SD6P0_118") (pintype "bidirectional"))
      (node (ref "R30") (pin "2") (pinfunction "2_2") (pintype "passive"))
    )
    (net (code "44") (name "I3-") (class "Default")
      (node (ref "C21") (pin "2") (pinfunction "2_2") (pintype "passive"))
      (node (ref "C7") (pin "1") (pinfunction "1_1") (pintype "passive"))
      (node (ref "MSP430F67791") (pin "119") (pinfunction "SD6N0_119") (pintype "bidirectional"))
      (node (ref "R31") (pin "2") (pinfunction "2_2") (pintype "passive"))
    )
    (net (code "45") (name "IN+") (class "Default")
      (node (ref "C14") (pin "1") (pinfunction "1_1") (pintype "passive"))
      (node (ref "C15") (pin "1") (pinfunction "1_1") (pintype "passive"))
      (node (ref "MSP430F67791") (pin "109") (pinfunction "SD3P0_109") (pintype "bidirectional"))
      (node (ref "R24") (pin "2") (pinfunction "2_2") (pintype "passive"))
    )
    (net (code "46") (name "IN-") (class "Default")
      (node (ref "C15") (pin "2") (pinfunction "2_2") (pintype "passive"))
      (node (ref "C4") (pin "1") (pinfunction "1_1") (pintype "passive"))
      (node (ref "MSP430F67791") (pin "110") (pinfunction "SD3N0_110") (pintype "bidirectional"))
      (node (ref "R25") (pin "2") (pinfunction "2_2") (pintype "passive"))
    )
    (net (code "47") (name "INT") (class "Default")
      (node (ref "JP10") (pin "1") (pinfunction "1_1") (pintype "passive"))
      (node (ref "JTAG") (pin "2") (pinfunction "2_2") (pintype "passive"))
    )
    (net (code "48") (name "IR_RXD") (class "Default")
      (node (ref "IRDA") (pin "P$3") (pinfunction "RXD_P$3") (pintype "bidirectional"))
      (node (ref "MSP430F67791") (pin "20") (pinfunction "P3.4/PM_UCA1RXD/PM_UCA1SOMI_20") (pintype "bidirectional"))
    )
    (net (code "49") (name "IR_SD") (class "Default")
      (node (ref "IRDA") (pin "P$4") (pinfunction "SD_P$4") (pintype "bidirectional"))
      (node (ref "MSP430F67791") (pin "19") (pinfunction "P3.3/PM_UCA1CLK_19") (pintype "bidirectional"))
    )
    (net (code "50") (name "IR_TXD") (class "Default")
      (node (ref "IRDA") (pin "P$2") (pinfunction "TXD_P$2") (pintype "bidirectional"))
      (node (ref "MSP430F67791") (pin "21") (pinfunction "P3.5/PM_UCA1TXD/PM_UCA1SIMO_21") (pintype "bidirectional"))
    )
    (net (code "51") (name "LED1") (class "Default")
      (node (ref "LED3") (pin "K") (pinfunction "C_K") (pintype "passive"))
      (node (ref "MSP430F67791") (pin "28") (pinfunction "P5.2/COM6_28") (pintype "bidirectional"))
    )
    (net (code "52") (name "LED2") (class "Default")
      (node (ref "LED2") (pin "K") (pinfunction "C_K") (pintype "passive"))
      (node (ref "MSP430F67791") (pin "27") (pinfunction "P5.1/COM5_27") (pintype "bidirectional"))
    )
    (net (code "53") (name "LED3") (class "Default")
      (node (ref "LED1") (pin "K") (pinfunction "C_K") (pintype "passive"))
      (node (ref "MSP430F67791") (pin "26") (pinfunction "P5.0/COM4_26") (pintype "bidirectional"))
    )
    (net (code "54") (name "LED4") (class "Default")
      (node (ref "LED4") (pin "K") (pinfunction "C_K") (pintype "passive"))
      (node (ref "MSP430F67791") (pin "45") (pinfunction "P4.7/PM_TA3.0_45") (pintype "bidirectional"))
    )
    (net (code "55") (name "LED5") (class "Default")
      (node (ref "LED5") (pin "K") (pinfunction "C_K") (pintype "passive"))
      (node (ref "MSP430F67791") (pin "15") (pinfunction "P2.7/PM_UCB0CLK_15") (pintype "bidirectional"))
    )
    (net (code "56") (name "LED6") (class "Default")
      (node (ref "LED6") (pin "K") (pinfunction "C_K") (pintype "passive"))
      (node (ref "MSP430F67791") (pin "12") (pinfunction "P2.4/PM_TA2.0_12") (pintype "bidirectional"))
    )
    (net (code "57") (name "LINE1") (class "Default")
      (node (ref "L1") (pin "1") (pinfunction "1_1") (pintype "passive"))
      (node (ref "LINE1") (pin "TP") (pinfunction "TP_TP") (pintype "input"))
      (node (ref "R1") (pin "2") (pinfunction "2_2") (pintype "passive"))
    )
    (net (code "58") (name "LINE2") (class "Default")
      (node (ref "L3") (pin "1") (pinfunction "1_1") (pintype "passive"))
      (node (ref "LINE2") (pin "TP") (pinfunction "TP_TP") (pintype "input"))
      (node (ref "R2") (pin "2") (pinfunction "2_2") (pintype "passive"))
    )
    (net (code "59") (name "LINE3") (class "Default")
      (node (ref "L5") (pin "1") (pinfunction "1_1") (pintype "passive"))
      (node (ref "LINE3") (pin "TP") (pinfunction "TP_TP") (pintype "input"))
      (node (ref "R3") (pin "2") (pinfunction "2_2") (pintype "passive"))
    )
    (net (code "60") (name "MCLK") (class "Default")
      (node (ref "MSP430F67791") (pin "7") (pinfunction "P1.4/MCLK/CB1/A4_7") (pintype "bidirectional"))
      (node (ref "SV2") (pin "4") (pinfunction "4_4") (pintype "passive"))
    )
    (net (code "61") (name "NEUTRAL") (class "Default")
      (node (ref "C102") (pin "-") (pinfunction "-_-") (pintype "passive"))
      (node (ref "C45") (pin "2") (pinfunction "2_2") (pintype "passive"))
      (node (ref "C48") (pin "2") (pinfunction "2_2") (pintype "passive"))
      (node (ref "C60") (pin "2") (pinfunction "2_2") (pintype "passive"))
      (node (ref "C61") (pin "2") (pinfunction "2_2") (pintype "passive"))
      (node (ref "C62") (pin "2") (pinfunction "2_2") (pintype "passive"))
      (node (ref "D17") (pin "A") (pinfunction "A_A") (pintype "passive"))
      (node (ref "D19") (pin "A") (pinfunction "A_A") (pintype "passive"))
      (node (ref "D21") (pin "A") (pinfunction "A_A") (pintype "passive"))
      (node (ref "D23") (pin "A") (pinfunction "A_A") (pintype "passive"))
      (node (ref "L6") (pin "1") (pinfunction "1_1") (pintype "passive"))
      (node (ref "NEUTRAL") (pin "TP") (pinfunction "TP_TP") (pintype "input"))
      (node (ref "R1") (pin "1") (pinfunction "1_1") (pintype "passive"))
      (node (ref "R2") (pin "1") (pinfunction "1_1") (pintype "passive"))
      (node (ref "R3") (pin "1") (pinfunction "1_1") (pintype "passive"))
      (node (ref "R37") (pin "1") (pinfunction "1_1") (pintype "passive"))
      (node (ref "R38") (pin "1") (pinfunction "1_1") (pintype "passive"))
      (node (ref "R39") (pin "2") (pinfunction "2_2") (pintype "passive"))
      (node (ref "R98") (pin "1") (pinfunction "1_1") (pintype "passive"))
      (node (ref "U$1") (pin "N") (pinfunction "N_N") (pintype "bidirectional"))
      (node (ref "U3") (pin "9") (pinfunction "GND_9") (pintype "power_in"))
    )
    (net (code "62") (name "Net-(AUXVCC3-Pad1)") (class "Default")
      (node (ref "AUXVCC3") (pin "1") (pinfunction "1_1") (pintype "passive"))
      (node (ref "D44") (pin "C") (pinfunction "C_C") (pintype "passive"))
    )
    (net (code "63") (name "Net-(C39-Pad2)") (class "Default")
      (node (ref "C39") (pin "2") (pinfunction "2_2") (pintype "passive"))
      (node (ref "R92") (pin "1") (pinfunction "1_1") (pintype "passive"))
    )
    (net (code "64") (name "Net-(C46-Pad2)") (class "Default")
      (node (ref "C46") (pin "2") (pinfunction "2_2") (pintype "passive"))
      (node (ref "R93") (pin "1") (pinfunction "1_1") (pintype "passive"))
    )
    (net (code "65") (name "Net-(C50-Pad2)") (class "Default")
      (node (ref "C50") (pin "2") (pinfunction "2_2") (pintype "passive"))
      (node (ref "R94") (pin "1") (pinfunction "1_1") (pintype "passive"))
    )
    (net (code "66") (name "Net-(C60-Pad1)") (class "Default")
      (node (ref "C60") (pin "1") (pinfunction "1_1") (pintype "passive"))
      (node (ref "R95") (pin "1") (pinfunction "1_1") (pintype "passive"))
    )
    (net (code "67") (name "Net-(C100-Pad+)") (class "Default")
      (node (ref "C100") (pin "+") (pinfunction "+_+") (pintype "passive"))
      (node (ref "U$1") (pin "22") (pinfunction "22_22") (pintype "bidirectional"))
    )
    (net (code "68") (name "Net-(C100-Pad-)") (class "Default")
      (node (ref "C100") (pin "-") (pinfunction "-_-") (pintype "passive"))
      (node (ref "U$1") (pin "26") (pinfunction "26_26") (pintype "bidirectional"))
    )
    (net (code "69") (name "Net-(D1-PadC)") (class "Default")
      (node (ref "D1") (pin "C") (pinfunction "C_C") (pintype "passive"))
      (node (ref "D40") (pin "A") (pinfunction "A_A") (pintype "passive"))
    )
    (net (code "70") (name "Net-(D2-PadC)") (class "Default")
      (node (ref "D2") (pin "C") (pinfunction "C_C") (pintype "passive"))
      (node (ref "D42") (pin "A") (pinfunction "A_A") (pintype "passive"))
    )
    (net (code "71") (name "Net-(D10-PadA)") (class "Default")
      (node (ref "D10") (pin "A") (pinfunction "A_A") (pintype "passive"))
      (node (ref "D43") (pin "C") (pinfunction "C_C") (pintype "passive"))
    )
    (net (code "72") (name "Net-(D11-PadA)") (class "Default")
      (node (ref "D11") (pin "A") (pinfunction "A_A") (pintype "passive"))
      (node (ref "D29") (pin "C") (pinfunction "C_C") (pintype "passive"))
    )
    (net (code "73") (name "Net-(D12-PadA)") (class "Default")
      (node (ref "D12") (pin "A") (pinfunction "A_A") (pintype "passive"))
      (node (ref "D31") (pin "C") (pinfunction "C_C") (pintype "passive"))
    )
    (net (code "74") (name "Net-(D13-PadA)") (class "Default")
      (node (ref "D13") (pin "A") (pinfunction "A_A") (pintype "passive"))
      (node (ref "D33") (pin "C") (pinfunction "C_C") (pintype "passive"))
    )
    (net (code "75") (name "Net-(D14-PadA)") (class "Default")
      (node (ref "D14") (pin "A") (pinfunction "A_A") (pintype "passive"))
      (node (ref "D35") (pin "C") (pinfunction "C_C") (pintype "passive"))
    )
    (net (code "76") (name "Net-(D15-PadA)") (class "Default")
      (node (ref "D15") (pin "A") (pinfunction "A_A") (pintype "passive"))
      (node (ref "D37") (pin "C") (pinfunction "C_C") (pintype "passive"))
    )
    (net (code "77") (name "Net-(D16-PadA)") (class "Default")
      (node (ref "D16") (pin "A") (pinfunction "A_A") (pintype "passive"))
      (node (ref "D39") (pin "C") (pinfunction "C_C") (pintype "passive"))
    )
    (net (code "78") (name "Net-(D17-PadC)") (class "Default")
      (node (ref "D17") (pin "C") (pinfunction "C_C") (pintype "passive"))
      (node (ref "D18") (pin "A") (pinfunction "A_A") (pintype "passive"))
      (node (ref "R92") (pin "2") (pinfunction "2_2") (pintype "passive"))
    )
    (net (code "79") (name "Net-(D19-PadC)") (class "Default")
      (node (ref "D19") (pin "C") (pinfunction "C_C") (pintype "passive"))
      (node (ref "D20") (pin "A") (pinfunction "A_A") (pintype "passive"))
      (node (ref "R93") (pin "2") (pinfunction "2_2") (pintype "passive"))
    )
    (net (code "80") (name "Net-(D21-PadC)") (class "Default")
      (node (ref "D21") (pin "C") (pinfunction "C_C") (pintype "passive"))
      (node (ref "D22") (pin "A") (pinfunction "A_A") (pintype "passive"))
      (node (ref "R94") (pin "2") (pinfunction "2_2") (pintype "passive"))
    )
    (net (code "81") (name "Net-(D24-C)") (class "Default")
      (node (ref "D24") (pin "1") (pinfunction "C_1") (pintype "passive"))
      (node (ref "R78") (pin "2") (pinfunction "2_2") (pintype "passive"))
      (node (ref "RS-232") (pin "3") (pinfunction "3_3") (pintype "passive"))
    )
    (net (code "82") (name "Net-(D25-A)") (class "Default")
      (node (ref "D25") (pin "2") (pinfunction "A_2") (pintype "passive"))
      (node (ref "RS-232") (pin "4") (pinfunction "4_4") (pintype "passive"))
    )
    (net (code "83") (name "Net-(D26-A)") (class "Default")
      (node (ref "D26") (pin "2") (pinfunction "A_2") (pintype "passive"))
      (node (ref "RS-232") (pin "7") (pinfunction "7_7") (pintype "passive"))
    )
    (net (code "84") (name "Net-(D27-C)") (class "Default")
      (node (ref "D27") (pin "1") (pinfunction "C_1") (pintype "passive"))
      (node (ref "R78") (pin "1") (pinfunction "1_1") (pintype "passive"))
      (node (ref "U2") (pin "2") (pinfunction "A_2") (pintype "passive"))
    )
    (net (code "85") (name "Net-(D28-PadA)") (class "Default")
      (node (ref "D28") (pin "A") (pinfunction "A_A") (pintype "passive"))
      (node (ref "D3") (pin "C") (pinfunction "C_C") (pintype "passive"))
    )
    (net (code "86") (name "Net-(D30-PadA)") (class "Default")
      (node (ref "D30") (pin "A") (pinfunction "A_A") (pintype "passive"))
      (node (ref "D4") (pin "C") (pinfunction "C_C") (pintype "passive"))
    )
    (net (code "87") (name "Net-(D32-PadA)") (class "Default")
      (node (ref "D32") (pin "A") (pinfunction "A_A") (pintype "passive"))
      (node (ref "D5") (pin "C") (pinfunction "C_C") (pintype "passive"))
    )
    (net (code "88") (name "Net-(D34-PadA)") (class "Default")
      (node (ref "D34") (pin "A") (pinfunction "A_A") (pintype "passive"))
      (node (ref "D6") (pin "C") (pinfunction "C_C") (pintype "passive"))
    )
    (net (code "89") (name "Net-(D36-PadA)") (class "Default")
      (node (ref "D36") (pin "A") (pinfunction "A_A") (pintype "passive"))
      (node (ref "D7") (pin "C") (pinfunction "C_C") (pintype "passive"))
    )
    (net (code "90") (name "Net-(D38-PadA)") (class "Default")
      (node (ref "D38") (pin "A") (pinfunction "A_A") (pintype "passive"))
      (node (ref "D8") (pin "C") (pinfunction "C_C") (pintype "passive"))
    )
    (net (code "91") (name "Net-(D41-PadC)") (class "Default")
      (node (ref "D41") (pin "C") (pinfunction "C_C") (pintype "passive"))
      (node (ref "D9") (pin "A") (pinfunction "A_A") (pintype "passive"))
    )
    (net (code "92") (name "Net-(D44-PadA)") (class "Default")
      (node (ref "D44") (pin "A") (pinfunction "A_A") (pintype "passive"))
      (node (ref "HD1") (pin "2") (pinfunction "2_2") (pintype "passive"))
    )
    (net (code "93") (name "Net-(IRDA-VCC1)") (class "Default")
      (node (ref "C52") (pin "1") (pinfunction "1_1") (pintype "passive"))
      (node (ref "IRDA") (pin "P$5") (pinfunction "VCC1_P$5") (pintype "bidirectional"))
      (node (ref "R47") (pin "2") (pinfunction "2_2") (pintype "passive"))
    )
    (net (code "94") (name "Net-(JP4-Pad1)") (class "Default")
      (node (ref "JP4") (pin "1") (pinfunction "1_1") (pintype "passive"))
      (node (ref "R48") (pin "2") (pinfunction "2_2") (pintype "passive"))
    )
    (net (code "95") (name "Net-(LED1-PadA)") (class "Default")
      (node (ref "LED1") (pin "A") (pinfunction "A_A") (pintype "passive"))
      (node (ref "R54") (pin "2") (pinfunction "2_2") (pintype "passive"))
    )
    (net (code "96") (name "Net-(LED2-PadA)") (class "Default")
      (node (ref "LED2") (pin "A") (pinfunction "A_A") (pintype "passive"))
      (node (ref "R55") (pin "2") (pinfunction "2_2") (pintype "passive"))
    )
    (net (code "97") (name "Net-(LED3-PadA)") (class "Default")
      (node (ref "LED3") (pin "A") (pinfunction "A_A") (pintype "passive"))
      (node (ref "R56") (pin "2") (pinfunction "2_2") (pintype "passive"))
    )
    (net (code "98") (name "Net-(LED4-PadA)") (class "Default")
      (node (ref "LED4") (pin "A") (pinfunction "A_A") (pintype "passive"))
      (node (ref "R59") (pin "2") (pinfunction "2_2") (pintype "passive"))
    )
    (net (code "99") (name "Net-(LED5-PadA)") (class "Default")
      (node (ref "LED5") (pin "A") (pinfunction "A_A") (pintype "passive"))
      (node (ref "R60") (pin "2") (pinfunction "2_2") (pintype "passive"))
    )
    (net (code "100") (name "Net-(LED6-PadA)") (class "Default")
      (node (ref "LED6") (pin "A") (pinfunction "A_A") (pintype "passive"))
      (node (ref "R61") (pin "2") (pinfunction "2_2") (pintype "passive"))
    )
    (net (code "101") (name "Net-(LED_ACT-PadA)") (class "Default")
      (node (ref "LED_ACT") (pin "A") (pinfunction "A_A") (pintype "passive"))
      (node (ref "R57") (pin "2") (pinfunction "2_2") (pintype "passive"))
    )
    (net (code "102") (name "Net-(LED_REACT-PadA)") (class "Default")
      (node (ref "LED_REACT") (pin "A") (pinfunction "A_A") (pintype "passive"))
      (node (ref "R58") (pin "2") (pinfunction "2_2") (pintype "passive"))
    )
    (net (code "103") (name "Net-(OPTO1-C)") (class "Default")
      (node (ref "OPTO1") (pin "2") (pinfunction "C_2") (pintype "passive"))
      (node (ref "R68") (pin "2") (pinfunction "2_2") (pintype "passive"))
    )
    (net (code "104") (name "Net-(OPTO1-COL)") (class "Default")
      (node (ref "OPTO1") (pin "4") (pinfunction "COL_4") (pintype "passive"))
      (node (ref "REACT") (pin "2") (pinfunction "2_2") (pintype "passive"))
    )
    (net (code "105") (name "Net-(OPTO1-EMIT)") (class "Default")
      (node (ref "OPTO1") (pin "3") (pinfunction "EMIT_3") (pintype "passive"))
      (node (ref "REACT") (pin "1") (pinfunction "1_1") (pintype "passive"))
    )
    (net (code "106") (name "Net-(OPTO2-C)") (class "Default")
      (node (ref "OPTO2") (pin "2") (pinfunction "C_2") (pintype "passive"))
      (node (ref "R72") (pin "2") (pinfunction "2_2") (pintype "passive"))
    )
    (net (code "107") (name "Net-(OPTO2-COL)") (class "Default")
      (node (ref "ACT") (pin "2") (pinfunction "2_2") (pintype "passive"))
      (node (ref "OPTO2") (pin "4") (pinfunction "COL_4") (pintype "passive"))
    )
    (net (code "108") (name "Net-(OPTO2-EMIT)") (class "Default")
      (node (ref "ACT") (pin "1") (pinfunction "1_1") (pintype "passive"))
      (node (ref "OPTO2") (pin "3") (pinfunction "EMIT_3") (pintype "passive"))
    )
    (net (code "109") (name "Net-(Q1-PadB)") (class "Default")
      (node (ref "Q1") (pin "B") (pinfunction "B_B") (pintype "passive"))
      (node (ref "R62") (pin "2") (pinfunction "2_2") (pintype "passive"))
      (node (ref "R63") (pin "1") (pinfunction "1_1") (pintype "passive"))
    )
    (net (code "110") (name "Net-(Q1-PadC)") (class "Default")
      (node (ref "Q1") (pin "C") (pinfunction "C_C") (pintype "passive"))
      (node (ref "R64") (pin "2") (pinfunction "2_2") (pintype "passive"))
    )
    (net (code "111") (name "Net-(Q2-PadB)") (class "Default")
      (node (ref "Q2") (pin "B") (pinfunction "B_B") (pintype "passive"))
      (node (ref "R69") (pin "2") (pinfunction "2_2") (pintype "passive"))
    )
    (net (code "112") (name "Net-(R/L7-Pad1)") (class "Default")
      (node (ref "R/L7") (pin "1") (pinfunction "1_1") (pintype "passive"))
      (node (ref "R20") (pin "2") (pinfunction "2_2") (pintype "passive"))
      (node (ref "R24") (pin "1") (pinfunction "1_1") (pintype "passive"))
    )
    (net (code "113") (name "Net-(R/L9-Pad1)") (class "Default")
      (node (ref "R/L9") (pin "1") (pinfunction "1_1") (pintype "passive"))
      (node (ref "R21") (pin "2") (pinfunction "2_2") (pintype "passive"))
      (node (ref "R26") (pin "1") (pinfunction "1_1") (pintype "passive"))
    )
    (net (code "114") (name "Net-(R/L11-Pad1)") (class "Default")
      (node (ref "R/L11") (pin "1") (pinfunction "1_1") (pintype "passive"))
      (node (ref "R22") (pin "2") (pinfunction "2_2") (pintype "passive"))
      (node (ref "R28") (pin "1") (pinfunction "1_1") (pintype "passive"))
    )
    (net (code "115") (name "Net-(R/L13-Pad1)") (class "Default")
      (node (ref "R/L13") (pin "1") (pinfunction "1_1") (pintype "passive"))
      (node (ref "R23") (pin "2") (pinfunction "2_2") (pintype "passive"))
      (node (ref "R30") (pin "1") (pinfunction "1_1") (pintype "passive"))
    )
    (net (code "116") (name "Net-(R5-Pad1)") (class "Default")
      (node (ref "R5") (pin "1") (pinfunction "1_1") (pintype "passive"))
      (node (ref "R6") (pin "2") (pinfunction "2_2") (pintype "passive"))
    )
    (net (code "117") (name "Net-(R6-Pad1)") (class "Default")
      (node (ref "R6") (pin "1") (pinfunction "1_1") (pintype "passive"))
      (node (ref "R7") (pin "2") (pinfunction "2_2") (pintype "passive"))
    )
    (net (code "118") (name "Net-(R8-Pad1)") (class "Default")
      (node (ref "R8") (pin "1") (pinfunction "1_1") (pintype "passive"))
      (node (ref "R9") (pin "2") (pinfunction "2_2") (pintype "passive"))
    )
    (net (code "119") (name "Net-(R10-Pad1)") (class "Default")
      (node (ref "R10") (pin "1") (pinfunction "1_1") (pintype "passive"))
      (node (ref "R16") (pin "2") (pinfunction "2_2") (pintype "passive"))
      (node (ref "R17") (pin "1") (pinfunction "1_1") (pintype "passive"))
    )
    (net (code "120") (name "Net-(R10-Pad2)") (class "Default")
      (node (ref "R10") (pin "2") (pinfunction "2_2") (pintype "passive"))
      (node (ref "R9") (pin "1") (pinfunction "1_1") (pintype "passive"))
    )
    (net (code "121") (name "Net-(R11-Pad1)") (class "Default")
      (node (ref "R11") (pin "1") (pinfunction "1_1") (pintype "passive"))
      (node (ref "R12") (pin "2") (pinfunction "2_2") (pintype "passive"))
    )
    (net (code "122") (name "Net-(R12-Pad1)") (class "Default")
      (node (ref "R12") (pin "1") (pinfunction "1_1") (pintype "passive"))
      (node (ref "R13") (pin "2") (pinfunction "2_2") (pintype "passive"))
    )
    (net (code "123") (name "Net-(R13-Pad1)") (class "Default")
      (node (ref "R13") (pin "1") (pinfunction "1_1") (pintype "passive"))
      (node (ref "R18") (pin "2") (pinfunction "2_2") (pintype "passive"))
      (node (ref "R19") (pin "1") (pinfunction "1_1") (pintype "passive"))
    )
    (net (code "124") (name "Net-(R14-Pad2)") (class "Default")
      (node (ref "R14") (pin "2") (pinfunction "2_2") (pintype "passive"))
      (node (ref "R15") (pin "1") (pinfunction "1_1") (pintype "passive"))
      (node (ref "R7") (pin "1") (pinfunction "1_1") (pintype "passive"))
    )
    (net (code "125") (name "Net-(R64-Pad1)") (class "Default")
      (node (ref "R64") (pin "1") (pinfunction "1_1") (pintype "passive"))
      (node (ref "R67") (pin "2") (pinfunction "2_2") (pintype "passive"))
      (node (ref "RS-232") (pin "2") (pinfunction "2_2") (pintype "passive"))
    )
    (net (code "126") (name "Net-(R73-Pad1)") (class "Default")
      (node (ref "R73") (pin "1") (pinfunction "1_1") (pintype "passive"))
      (node (ref "RF1") (pin "4") (pinfunction "4_4") (pintype "passive"))
    )
    (net (code "127") (name "Net-(R74-Pad2)") (class "Default")
      (node (ref "R74") (pin "2") (pinfunction "2_2") (pintype "passive"))
      (node (ref "RF2") (pin "3") (pinfunction "3_3") (pintype "passive"))
    )
    (net (code "128") (name "Net-(R75-Pad1)") (class "Default")
      (node (ref "R75") (pin "1") (pinfunction "1_1") (pintype "passive"))
      (node (ref "RF2") (pin "6") (pinfunction "6_6") (pintype "passive"))
    )
    (net (code "129") (name "Net-(R76-Pad2)") (class "Default")
      (node (ref "R76") (pin "2") (pinfunction "2_2") (pintype "passive"))
      (node (ref "RF2") (pin "5") (pinfunction "5_5") (pintype "passive"))
    )
    (net (code "130") (name "Net-(R77-Pad1)") (class "Default")
      (node (ref "R77") (pin "1") (pinfunction "1_1") (pintype "passive"))
      (node (ref "RF1") (pin "6") (pinfunction "6_6") (pintype "passive"))
    )
    (net (code "131") (name "Net-(R79-Pad2)") (class "Default")
      (node (ref "R79") (pin "2") (pinfunction "2_2") (pintype "passive"))
      (node (ref "RF1") (pin "7") (pinfunction "7_7") (pintype "passive"))
    )
    (net (code "132") (name "Net-(R80-Pad2)") (class "Default")
      (node (ref "R80") (pin "2") (pinfunction "2_2") (pintype "passive"))
      (node (ref "RF2") (pin "7") (pinfunction "7_7") (pintype "passive"))
    )
    (net (code "133") (name "Net-(R81-Pad1)") (class "Default")
      (node (ref "R81") (pin "1") (pinfunction "1_1") (pintype "passive"))
      (node (ref "RF2") (pin "8") (pinfunction "8_8") (pintype "passive"))
    )
    (net (code "134") (name "Net-(R82-Pad2)") (class "Default")
      (node (ref "R82") (pin "2") (pinfunction "2_2") (pintype "passive"))
      (node (ref "RF2") (pin "9") (pinfunction "9_9") (pintype "passive"))
    )
    (net (code "135") (name "Net-(R83-Pad1)") (class "Default")
      (node (ref "R83") (pin "1") (pinfunction "1_1") (pintype "passive"))
      (node (ref "RF2") (pin "10") (pinfunction "10_10") (pintype "passive"))
    )
    (net (code "136") (name "Net-(R84-Pad1)") (class "Default")
      (node (ref "R84") (pin "1") (pinfunction "1_1") (pintype "passive"))
      (node (ref "RF2") (pin "12") (pinfunction "12_12") (pintype "passive"))
    )
    (net (code "137") (name "Net-(R85-Pad1)") (class "Default")
      (node (ref "R85") (pin "1") (pinfunction "1_1") (pintype "passive"))
      (node (ref "RF2") (pin "14") (pinfunction "14_14") (pintype "passive"))
    )
    (net (code "138") (name "Net-(R86-Pad1)") (class "Default")
      (node (ref "R86") (pin "1") (pinfunction "1_1") (pintype "passive"))
      (node (ref "RF2") (pin "16") (pinfunction "16_16") (pintype "passive"))
    )
    (net (code "139") (name "Net-(R87-Pad2)") (class "Default")
      (node (ref "R87") (pin "2") (pinfunction "2_2") (pintype "passive"))
      (node (ref "RF1") (pin "15") (pinfunction "15_15") (pintype "passive"))
    )
    (net (code "140") (name "Net-(R88-Pad1)") (class "Default")
      (node (ref "R88") (pin "1") (pinfunction "1_1") (pintype "passive"))
      (node (ref "RF2") (pin "18") (pinfunction "18_18") (pintype "passive"))
    )
    (net (code "141") (name "Net-(R89-Pad1)") (class "Default")
      (node (ref "R89") (pin "1") (pinfunction "1_1") (pintype "passive"))
      (node (ref "RF1") (pin "18") (pinfunction "18_18") (pintype "passive"))
    )
    (net (code "142") (name "Net-(R90-Pad2)") (class "Default")
      (node (ref "R90") (pin "2") (pinfunction "2_2") (pintype "passive"))
      (node (ref "RF1") (pin "19") (pinfunction "19_19") (pintype "passive"))
    )
    (net (code "143") (name "Net-(R91-Pad1)") (class "Default")
      (node (ref "R91") (pin "1") (pinfunction "1_1") (pintype "passive"))
      (node (ref "RF2") (pin "20") (pinfunction "20_20") (pintype "passive"))
    )
    (net (code "144") (name "Net-(R96-Pad1)") (class "Default")
      (node (ref "R96") (pin "1") (pinfunction "1_1") (pintype "passive"))
      (node (ref "R97") (pin "2") (pinfunction "2_2") (pintype "passive"))
    )
    (net (code "145") (name "Net-(U1-A)") (class "Default")
      (node (ref "R65") (pin "2") (pinfunction "2_2") (pintype "passive"))
      (node (ref "U1") (pin "2") (pinfunction "A_2") (pintype "passive"))
    )
    (net (code "146") (name "Net-(U1-C)") (class "Default")
      (node (ref "Q2") (pin "E") (pinfunction "E_E") (pintype "passive"))
      (node (ref "U1") (pin "3") (pinfunction "C_3") (pintype "passive"))
    )
    (net (code "147") (name "Net-(U1-VB)") (class "Default")
      (node (ref "R66") (pin "1") (pinfunction "1_1") (pintype "passive"))
      (node (ref "U1") (pin "7") (pinfunction "VB_7") (pintype "passive"))
    )
    (net (code "148") (name "Net-(U1-VO)") (class "Default")
      (node (ref "R62") (pin "1") (pinfunction "1_1") (pintype "passive"))
      (node (ref "U1") (pin "6") (pinfunction "VO_6") (pintype "passive"))
    )
    (net (code "149") (name "Net-(U3-BOOT)") (class "Default")
      (node (ref "C47") (pin "1") (pinfunction "1_1") (pintype "passive"))
      (node (ref "U3") (pin "1") (pinfunction "BOOT_1") (pintype "output"))
    )
    (net (code "150") (name "Net-(U3-COMP)") (class "Default")
      (node (ref "C61") (pin "1") (pinfunction "1_1") (pintype "passive"))
      (node (ref "R95") (pin "2") (pinfunction "2_2") (pintype "passive"))
      (node (ref "U3") (pin "8") (pinfunction "COMP_8") (pintype "output"))
    )
    (net (code "151") (name "Net-(U3-EN)") (class "Default")
      (node (ref "R35") (pin "1") (pinfunction "1_1") (pintype "passive"))
      (node (ref "R37") (pin "2") (pinfunction "2_2") (pintype "passive"))
      (node (ref "U3") (pin "3") (pinfunction "EN_3") (pintype "input"))
    )
    (net (code "152") (name "Net-(U3-PH)") (class "Default")
      (node (ref "C47") (pin "2") (pinfunction "2_2") (pintype "passive"))
      (node (ref "D23") (pin "C") (pinfunction "C_C") (pintype "passive"))
      (node (ref "L7") (pin "1") (pinfunction "1_1") (pintype "passive"))
      (node (ref "U3") (pin "10") (pinfunction "PH_10") (pintype "input"))
    )
    (net (code "153") (name "Net-(U3-RT{slash}CLK)") (class "Default")
      (node (ref "R38") (pin "2") (pinfunction "2_2") (pintype "passive"))
      (node (ref "U3") (pin "5") (pinfunction "RT/CLK_5") (pintype "input"))
    )
    (net (code "154") (name "Net-(U3-SS{slash}TR)") (class "Default")
      (node (ref "C45") (pin "1") (pinfunction "1_1") (pintype "passive"))
      (node (ref "U3") (pin "4") (pinfunction "SS/TR_4") (pintype "input"))
    )
    (net (code "155") (name "Net-(U3-VSENSE)") (class "Default")
      (node (ref "R97") (pin "1") (pinfunction "1_1") (pintype "passive"))
      (node (ref "R98") (pin "2") (pinfunction "2_2") (pintype "passive"))
      (node (ref "U3") (pin "7") (pinfunction "VSENSE_7") (pintype "input"))
    )
    (net (code "156") (name "P1+1") (class "Default")
      (node (ref "C39") (pin "1") (pinfunction "1_1") (pintype "passive"))
      (node (ref "L1") (pin "2") (pinfunction "2_2") (pintype "passive"))
      (node (ref "R5") (pin "2") (pinfunction "2_2") (pintype "passive"))
    )
    (net (code "157") (name "P2+1") (class "Default")
      (node (ref "C46") (pin "1") (pinfunction "1_1") (pintype "passive"))
      (node (ref "L3") (pin "2") (pinfunction "2_2") (pintype "passive"))
      (node (ref "R8") (pin "2") (pinfunction "2_2") (pintype "passive"))
    )
    (net (code "158") (name "P3+1") (class "Default")
      (node (ref "C50") (pin "1") (pinfunction "1_1") (pintype "passive"))
      (node (ref "L5") (pin "2") (pinfunction "2_2") (pintype "passive"))
      (node (ref "R11") (pin "2") (pinfunction "2_2") (pintype "passive"))
      (node (ref "U$1") (pin "L") (pinfunction "L_L") (pintype "bidirectional"))
    )
    (net (code "159") (name "R13") (class "Default")
      (node (ref "MSP430F67791") (pin "32") (pinfunction "P5.5/SD0DIO/LCDREF/R13_32") (pintype "bidirectional"))
      (node (ref "R43") (pin "1") (pinfunction "1_1") (pintype "passive"))
      (node (ref "R46") (pin "2") (pinfunction "2_2") (pintype "passive"))
    )
    (net (code "160") (name "R23") (class "Default")
      (node (ref "MSP430F67791") (pin "31") (pinfunction "P5.4/SDCLK/R23_31") (pintype "bidirectional"))
      (node (ref "R42") (pin "1") (pinfunction "1_1") (pintype "passive"))
      (node (ref "R43") (pin "2") (pinfunction "2_2") (pintype "passive"))
    )
    (net (code "161") (name "R33") (class "Default")
      (node (ref "C49") (pin "1") (pinfunction "1_1") (pintype "passive"))
      (node (ref "MSP430F67791") (pin "30") (pinfunction "LCDCAP/R33_30") (pintype "bidirectional"))
      (node (ref "R42") (pin "2") (pinfunction "2_2") (pintype "passive"))
    )
    (net (code "162") (name "REACT") (class "Default")
      (node (ref "JP11") (pin "1") (pinfunction "1_1") (pintype "passive"))
      (node (ref "LED_REACT") (pin "K") (pinfunction "C_K") (pintype "passive"))
      (node (ref "MSP430F67791") (pin "41") (pinfunction "P4.3/PM_UCA3CLK_41") (pintype "bidirectional"))
      (node (ref "R68") (pin "1") (pinfunction "1_1") (pintype "passive"))
    )
    (net (code "163") (name "RESET") (class "Default")
      (node (ref "C53") (pin "2") (pinfunction "2_2") (pintype "passive"))
      (node (ref "JP5") (pin "3") (pinfunction "3_3") (pintype "passive"))
      (node (ref "JTAG") (pin "11") (pinfunction "11_11") (pintype "passive"))
      (node (ref "R51") (pin "2") (pinfunction "2_2") (pintype "passive"))
      (node (ref "RESET") (pin "1") (pinfunction "P_1") (pintype "passive"))
    )
    (net (code "164") (name "RF_CCA") (class "Default")
      (node (ref "MSP430F67791") (pin "90") (pinfunction "TA2.1/P11.3_90") (pintype "bidirectional"))
      (node (ref "R83") (pin "2") (pinfunction "2_2") (pintype "passive"))
    )
    (net (code "165") (name "RF_CLK") (class "Default")
      (node (ref "MSP430F67791") (pin "44") (pinfunction "P4.6/PM_UCB1CLK_44") (pintype "bidirectional"))
      (node (ref "R86") (pin "2") (pinfunction "2_2") (pintype "passive"))
    )
    (net (code "166") (name "RF_CS") (class "Default")
      (node (ref "MSP430F67791") (pin "94") (pinfunction "BSL_RX/PM_TA0.1/P2.1_94") (pintype "bidirectional"))
      (node (ref "R85") (pin "2") (pinfunction "2_2") (pintype "passive"))
    )
    (net (code "167") (name "RF_FIFO") (class "Default")
      (node (ref "MSP430F67791") (pin "40") (pinfunction "P4.2/PM_UCA3TXD/PM_UCA3SIMO_40") (pintype "bidirectional"))
      (node (ref "R75") (pin "2") (pinfunction "2_2") (pintype "passive"))
      (node (ref "R80") (pin "1") (pinfunction "1_1") (pintype "passive"))
    )
    (net (code "168") (name "RF_FIFOP") (class "Default")
      (node (ref "MSP430F67791") (pin "39") (pinfunction "P4.1/PM_UCA3RXD/M_UCA3SOMI_39") (pintype "bidirectional"))
      (node (ref "R81") (pin "2") (pinfunction "2_2") (pintype "passive"))
      (node (ref "R82") (pin "1") (pinfunction "1_1") (pintype "passive"))
    )
    (net (code "169") (name "RF_GPIO1") (class "Default")
      (node (ref "MSP430F67791") (pin "96") (pinfunction "PM_TA1.0/P2.3_96") (pintype "bidirectional"))
      (node (ref "R90") (pin "1") (pinfunction "1_1") (pintype "passive"))
    )
    (net (code "170") (name "RF_GPIO2") (class "Default")
      (node (ref "MSP430F67791") (pin "95") (pinfunction "PM_TA0.2/P2.2_95") (pintype "bidirectional"))
      (node (ref "R89") (pin "2") (pinfunction "2_2") (pintype "passive"))
    )
    (net (code "171") (name "RF_RESETCC") (class "Default")
      (node (ref "MSP430F67791") (pin "89") (pinfunction "TA1.1/P11.2_89") (pintype "bidirectional"))
      (node (ref "R76") (pin "1") (pinfunction "1_1") (pintype "passive"))
      (node (ref "R87") (pin "1") (pinfunction "1_1") (pintype "passive"))
    )
    (net (code "172") (name "RF_SFD") (class "Default")
      (node (ref "MSP430F67791") (pin "93") (pinfunction "BSL_TX/PM_TA0.0/P2.0_93") (pintype "bidirectional"))
      (node (ref "R84") (pin "2") (pinfunction "2_2") (pintype "passive"))
    )
    (net (code "173") (name "RF_SIMO") (class "Default")
      (node (ref "MSP430F67791") (pin "43") (pinfunction "P4.5/PM_UCB1SIMO/PM_UCB1SDA_43") (pintype "bidirectional"))
      (node (ref "R88") (pin "2") (pinfunction "2_2") (pintype "passive"))
    )
    (net (code "174") (name "RF_SOMI") (class "Default")
      (node (ref "MSP430F67791") (pin "42") (pinfunction "P4.4/PM_UCB1SOMI/PM_UCB1SCL_42") (pintype "bidirectional"))
      (node (ref "R91") (pin "2") (pinfunction "2_2") (pintype "passive"))
    )
    (net (code "175") (name "RF_VREG_EN") (class "Default")
      (node (ref "MSP430F67791") (pin "88") (pinfunction "CB3/TA3.1/P11.1_88") (pintype "bidirectional"))
      (node (ref "R74") (pin "1") (pinfunction "1_1") (pintype "passive"))
    )
    (net (code "176") (name "RS232_RXD") (class "Default")
      (node (ref "MSP430F67791") (pin "16") (pinfunction "P3.0/PM_UCA0RXD/PM_UCA0SOMI_16") (pintype "bidirectional"))
      (node (ref "RX_EN") (pin "2") (pinfunction "2_2") (pintype "passive"))
    )
    (net (code "177") (name "RS232_TXD") (class "Default")
      (node (ref "MSP430F67791") (pin "17") (pinfunction "P3.1/PM_UCA0TXD/PM_UCA0SIMO_17") (pintype "bidirectional"))
      (node (ref "TX_EN") (pin "2") (pinfunction "2_2") (pintype "passive"))
    )
    (net (code "178") (name "RTCCLK") (class "Default")
      (node (ref "MSP430F67791") (pin "92") (pinfunction "TRCCLK/TACLK/P11.5_92") (pintype "bidirectional"))
      (node (ref "SV2") (pin "2") (pinfunction "2_2") (pintype "passive"))
    )
    (net (code "179") (name "S0") (class "Default")
      (node (ref "LCD1") (pin "1") (pinfunction "1_1") (pintype "bidirectional"))
      (node (ref "MSP430F67791") (pin "87") (pinfunction "S0/P11.0_87") (pintype "bidirectional"))
    )
    (net (code "180") (name "S1") (class "Default")
      (node (ref "LCD1") (pin "2") (pinfunction "2_2") (pintype "bidirectional"))
      (node (ref "MSP430F67791") (pin "86") (pinfunction "S1/P10.7_86") (pintype "bidirectional"))
    )
    (net (code "181") (name "S2") (class "Default")
      (node (ref "LCD1") (pin "3") (pinfunction "3_3") (pintype "bidirectional"))
      (node (ref "MSP430F67791") (pin "85") (pinfunction "S2/P10.6_85") (pintype "bidirectional"))
    )
    (net (code "182") (name "S3") (class "Default")
      (node (ref "LCD1") (pin "4") (pinfunction "4_4") (pintype "bidirectional"))
      (node (ref "MSP430F67791") (pin "84") (pinfunction "S3/P10.5_84") (pintype "bidirectional"))
    )
    (net (code "183") (name "S4") (class "Default")
      (node (ref "LCD1") (pin "5") (pinfunction "5_5") (pintype "bidirectional"))
      (node (ref "MSP430F67791") (pin "83") (pinfunction "S4/P10.4_83") (pintype "bidirectional"))
    )
    (net (code "184") (name "S5") (class "Default")
      (node (ref "LCD1") (pin "6") (pinfunction "6_6") (pintype "bidirectional"))
      (node (ref "MSP430F67791") (pin "82") (pinfunction "S5/P10.3_82") (pintype "bidirectional"))
    )
    (net (code "185") (name "S6") (class "Default")
      (node (ref "LCD1") (pin "7") (pinfunction "7_7") (pintype "bidirectional"))
      (node (ref "MSP430F67791") (pin "81") (pinfunction "S6/P10.2_81") (pintype "bidirectional"))
    )
    (net (code "186") (name "S7") (class "Default")
      (node (ref "LCD1") (pin "8") (pinfunction "8_8") (pintype "bidirectional"))
      (node (ref "MSP430F67791") (pin "80") (pinfunction "S7/P10.1_80") (pintype "bidirectional"))
    )
    (net (code "187") (name "S8") (class "Default")
      (node (ref "LCD1") (pin "9") (pinfunction "9_9") (pintype "bidirectional"))
      (node (ref "MSP430F67791") (pin "79") (pinfunction "S8/P10.0_79") (pintype "bidirectional"))
    )
    (net (code "188") (name "S9") (class "Default")
      (node (ref "LCD1") (pin "10") (pinfunction "10_10") (pintype "bidirectional"))
      (node (ref "MSP430F67791") (pin "78") (pinfunction "S9/P9.7_78") (pintype "bidirectional"))
    )
    (net (code "189") (name "S10") (class "Default")
      (node (ref "LCD1") (pin "11") (pinfunction "11_11") (pintype "bidirectional"))
      (node (ref "MSP430F67791") (pin "77") (pinfunction "S10/P9.6_77") (pintype "bidirectional"))
    )
    (net (code "190") (name "S11") (class "Default")
      (node (ref "LCD1") (pin "12") (pinfunction "12_12") (pintype "bidirectional"))
      (node (ref "MSP430F67791") (pin "76") (pinfunction "S11/P9.5_76") (pintype "bidirectional"))
    )
    (net (code "191") (name "S12") (class "Default")
      (node (ref "LCD1") (pin "13") (pinfunction "13_13") (pintype "bidirectional"))
      (node (ref "MSP430F67791") (pin "75") (pinfunction "S12/P9.4_75") (pintype "bidirectional"))
    )
    (net (code "192") (name "S13") (class "Default")
      (node (ref "LCD1") (pin "14") (pinfunction "14_14") (pintype "bidirectional"))
      (node (ref "MSP430F67791") (pin "74") (pinfunction "S13/P9.3_74") (pintype "bidirectional"))
    )
    (net (code "193") (name "S14") (class "Default")
      (node (ref "LCD1") (pin "15") (pinfunction "15_15") (pintype "bidirectional"))
      (node (ref "MSP430F67791") (pin "73") (pinfunction "S14/P9.2_73") (pintype "bidirectional"))
    )
    (net (code "194") (name "S15") (class "Default")
      (node (ref "LCD1") (pin "16") (pinfunction "16_16") (pintype "bidirectional"))
      (node (ref "MSP430F67791") (pin "72") (pinfunction "S15/P9.1_72") (pintype "bidirectional"))
    )
    (net (code "195") (name "S16") (class "Default")
      (node (ref "LCD1") (pin "17") (pinfunction "17_17") (pintype "bidirectional"))
      (node (ref "MSP430F67791") (pin "71") (pinfunction "S16/P9.0_71") (pintype "bidirectional"))
    )
    (net (code "196") (name "S17") (class "Default")
      (node (ref "LCD1") (pin "18") (pinfunction "18_18") (pintype "bidirectional"))
      (node (ref "MSP430F67791") (pin "68") (pinfunction "S17/P8.7_68") (pintype "bidirectional"))
    )
    (net (code "197") (name "S18") (class "Default")
      (node (ref "LCD1") (pin "19") (pinfunction "19_19") (pintype "bidirectional"))
      (node (ref "MSP430F67791") (pin "67") (pinfunction "S18/P8.6_67") (pintype "bidirectional"))
    )
    (net (code "198") (name "S19") (class "Default")
      (node (ref "LCD1") (pin "20") (pinfunction "20_20") (pintype "bidirectional"))
      (node (ref "MSP430F67791") (pin "66") (pinfunction "S19/P8.5_66") (pintype "bidirectional"))
    )
    (net (code "199") (name "S20") (class "Default")
      (node (ref "LCD1") (pin "21") (pinfunction "21_21") (pintype "bidirectional"))
      (node (ref "MSP430F67791") (pin "65") (pinfunction "S20/P8.4_65") (pintype "bidirectional"))
    )
    (net (code "200") (name "S21") (class "Default")
      (node (ref "LCD1") (pin "22") (pinfunction "22_22") (pintype "bidirectional"))
      (node (ref "MSP430F67791") (pin "64") (pinfunction "P8.3/S21_64") (pintype "bidirectional"))
    )
    (net (code "201") (name "S22") (class "Default")
      (node (ref "LCD1") (pin "23") (pinfunction "23_23") (pintype "bidirectional"))
      (node (ref "MSP430F67791") (pin "63") (pinfunction "P8.2/S22_63") (pintype "bidirectional"))
    )
    (net (code "202") (name "S23") (class "Default")
      (node (ref "LCD1") (pin "24") (pinfunction "24_24") (pintype "bidirectional"))
      (node (ref "MSP430F67791") (pin "62") (pinfunction "P8.1/S23_62") (pintype "bidirectional"))
    )
    (net (code "203") (name "S24") (class "Default")
      (node (ref "LCD1") (pin "29") (pinfunction "29_29") (pintype "bidirectional"))
      (node (ref "MSP430F67791") (pin "61") (pinfunction "P8.0/S24_61") (pintype "bidirectional"))
    )
    (net (code "204") (name "S25") (class "Default")
      (node (ref "LCD1") (pin "30") (pinfunction "30_30") (pintype "bidirectional"))
      (node (ref "MSP430F67791") (pin "60") (pinfunction "P7.7/S25_60") (pintype "bidirectional"))
    )
    (net (code "205") (name "S26") (class "Default")
      (node (ref "LCD1") (pin "31") (pinfunction "31_31") (pintype "bidirectional"))
      (node (ref "MSP430F67791") (pin "59") (pinfunction "P7.6/S26_59") (pintype "bidirectional"))
    )
    (net (code "206") (name "S27") (class "Default")
      (node (ref "LCD1") (pin "32") (pinfunction "32_32") (pintype "bidirectional"))
      (node (ref "MSP430F67791") (pin "58") (pinfunction "P7.5/S27_58") (pintype "bidirectional"))
    )
    (net (code "207") (name "S28") (class "Default")
      (node (ref "LCD1") (pin "33") (pinfunction "33_33") (pintype "bidirectional"))
      (node (ref "MSP430F67791") (pin "57") (pinfunction "P7.4/S28_57") (pintype "bidirectional"))
    )
    (net (code "208") (name "S29") (class "Default")
      (node (ref "LCD1") (pin "34") (pinfunction "34_34") (pintype "bidirectional"))
      (node (ref "MSP430F67791") (pin "56") (pinfunction "P7.3/S29_56") (pintype "bidirectional"))
    )
    (net (code "209") (name "S30") (class "Default")
      (node (ref "LCD1") (pin "35") (pinfunction "35_35") (pintype "bidirectional"))
      (node (ref "MSP430F67791") (pin "55") (pinfunction "P7.2/S30_55") (pintype "bidirectional"))
    )
    (net (code "210") (name "S31") (class "Default")
      (node (ref "LCD1") (pin "36") (pinfunction "36_36") (pintype "bidirectional"))
      (node (ref "MSP430F67791") (pin "54") (pinfunction "P7.1/S31_54") (pintype "bidirectional"))
    )
    (net (code "211") (name "S32") (class "Default")
      (node (ref "LCD1") (pin "37") (pinfunction "37_37") (pintype "bidirectional"))
      (node (ref "MSP430F67791") (pin "53") (pinfunction "P7.0/S32_53") (pintype "bidirectional"))
    )
    (net (code "212") (name "S33") (class "Default")
      (node (ref "LCD1") (pin "38") (pinfunction "38_38") (pintype "bidirectional"))
      (node (ref "MSP430F67791") (pin "52") (pinfunction "P6.7/S33_52") (pintype "bidirectional"))
    )
    (net (code "213") (name "S34") (class "Default")
      (node (ref "LCD1") (pin "39") (pinfunction "39_39") (pintype "bidirectional"))
      (node (ref "MSP430F67791") (pin "51") (pinfunction "P6.6/S34_51") (pintype "bidirectional"))
    )
    (net (code "214") (name "S35") (class "Default")
      (node (ref "LCD1") (pin "40") (pinfunction "40_40") (pintype "bidirectional"))
      (node (ref "MSP430F67791") (pin "50") (pinfunction "P6.5/S35_50") (pintype "bidirectional"))
    )
    (net (code "215") (name "S36") (class "Default")
      (node (ref "LCD1") (pin "41") (pinfunction "41_41") (pintype "bidirectional"))
      (node (ref "MSP430F67791") (pin "49") (pinfunction "P6.4/S36_49") (pintype "bidirectional"))
    )
    (net (code "216") (name "S37") (class "Default")
      (node (ref "LCD1") (pin "42") (pinfunction "42_42") (pintype "bidirectional"))
      (node (ref "MSP430F67791") (pin "48") (pinfunction "P6.3/SD6DIO/S37_48") (pintype "bidirectional"))
    )
    (net (code "217") (name "S38") (class "Default")
      (node (ref "LCD1") (pin "43") (pinfunction "43_43") (pintype "bidirectional"))
      (node (ref "MSP430F67791") (pin "47") (pinfunction "P6.2/SD5DIOS38_47") (pintype "bidirectional"))
    )
    (net (code "218") (name "S39") (class "Default")
      (node (ref "LCD1") (pin "44") (pinfunction "44_44") (pintype "bidirectional"))
      (node (ref "MSP430F67791") (pin "46") (pinfunction "P6.1/SD4DIO/S39_46") (pintype "bidirectional"))
    )
    (net (code "219") (name "SCL") (class "Default")
      (node (ref "IC1") (pin "6") (pinfunction "SCL_6") (pintype "input"))
      (node (ref "JP2") (pin "1") (pinfunction "1_1") (pintype "passive"))
      (node (ref "MSP430F67791") (pin "13") (pinfunction "P2.5/PM_UCB0SOMI/PM_UCB0SCL_13") (pintype "bidirectional"))
      (node (ref "R40") (pin "1") (pinfunction "1_1") (pintype "passive"))
    )
    (net (code "220") (name "SDA") (class "Default")
      (node (ref "IC1") (pin "5") (pinfunction "SDA_5") (pintype "bidirectional"))
      (node (ref "JP2") (pin "2") (pinfunction "2_2") (pintype "passive"))
      (node (ref "MSP430F67791") (pin "14") (pinfunction "P2.6/PM_UCB0SIMO/PM_UCB0SDA_14") (pintype "bidirectional"))
      (node (ref "R41") (pin "1") (pinfunction "1_1") (pintype "passive"))
    )
    (net (code "221") (name "SMCLK") (class "Default")
      (node (ref "MSP430F67791") (pin "6") (pinfunction "P1.5/SMCLK/CB0/A5_6") (pintype "bidirectional"))
      (node (ref "SV2") (pin "5") (pinfunction "5_5") (pintype "passive"))
    )
    (net (code "222") (name "TCK") (class "Default")
      (node (ref "JP6") (pin "3") (pinfunction "3_3") (pintype "passive"))
      (node (ref "JTAG") (pin "7") (pinfunction "7_7") (pintype "passive"))
      (node (ref "R48") (pin "1") (pinfunction "1_1") (pintype "passive"))
    )
    (net (code "223") (name "TDI") (class "Default")
      (node (ref "JP8") (pin "3") (pinfunction "3_3") (pintype "passive"))
      (node (ref "JTAG") (pin "3") (pinfunction "3_3") (pintype "passive"))
    )
    (net (code "224") (name "TDO") (class "Default")
      (node (ref "JP5") (pin "1") (pinfunction "1_1") (pintype "passive"))
      (node (ref "JP9") (pin "3") (pinfunction "3_3") (pintype "passive"))
      (node (ref "JTAG") (pin "1") (pinfunction "1_1") (pintype "passive"))
    )
    (net (code "225") (name "TEST{slash}SBWTCK") (class "Default")
      (node (ref "JP4") (pin "2") (pinfunction "2_2") (pintype "passive"))
      (node (ref "JP4") (pin "3") (pinfunction "3_3") (pintype "passive"))
      (node (ref "JTAG") (pin "8") (pinfunction "8_8") (pintype "passive"))
      (node (ref "MSP430F67791") (pin "97") (pinfunction "SBWTCK/TEST_97") (pintype "bidirectional"))
    )
    (net (code "226") (name "TMS") (class "Default")
      (node (ref "JP7") (pin "3") (pinfunction "3_3") (pintype "passive"))
      (node (ref "JTAG") (pin "5") (pinfunction "5_5") (pintype "passive"))
    )
    (net (code "227") (name "UART_RX") (class "Default")
      (node (ref "R70") (pin "1") (pinfunction "1_1") (pintype "passive"))
      (node (ref "R71") (pin "2") (pinfunction "2_2") (pintype "passive"))
      (node (ref "RX_EN") (pin "1") (pinfunction "1_1") (pintype "passive"))
      (node (ref "U2") (pin "6") (pinfunction "VO_6") (pintype "passive"))
    )
    (net (code "228") (name "UART_TX") (class "Default")
      (node (ref "R69") (pin "1") (pinfunction "1_1") (pintype "passive"))
      (node (ref "TX_EN") (pin "1") (pinfunction "1_1") (pintype "passive"))
    )
    (net (code "229") (name "V1+") (class "Default")
      (node (ref "C1") (pin "1") (pinfunction "1_1") (pintype "passive"))
      (node (ref "C8") (pin "1") (pinfunction "1_1") (pintype "passive"))
      (node (ref "MSP430F67791") (pin "103") (pinfunction "SD0P0_103") (pintype "bidirectional"))
      (node (ref "R14") (pin "1") (pinfunction "1_1") (pintype "passive"))
    )
    (net (code "230") (name "V1-") (class "Default")
      (node (ref "C8") (pin "2") (pinfunction "2_2") (pintype "passive"))
      (node (ref "C9") (pin "1") (pinfunction "1_1") (pintype "passive"))
      (node (ref "MSP430F67791") (pin "104") (pinfunction "SDPN0_104") (pintype "bidirectional"))
      (node (ref "R32") (pin "1") (pinfunction "1_1") (pintype "passive"))
    )
    (net (code "231") (name "V2+") (class "Default")
      (node (ref "C10") (pin "1") (pinfunction "1_1") (pintype "passive"))
      (node (ref "C2") (pin "1") (pinfunction "1_1") (pintype "passive"))
      (node (ref "MSP430F67791") (pin "105") (pinfunction "SD1P0_105") (pintype "bidirectional"))
      (node (ref "R16") (pin "1") (pinfunction "1_1") (pintype "passive"))
    )
    (net (code "232") (name "V2-") (class "Default")
      (node (ref "C10") (pin "2") (pinfunction "2_2") (pintype "passive"))
      (node (ref "C11") (pin "1") (pinfunction "1_1") (pintype "passive"))
      (node (ref "MSP430F67791") (pin "106") (pinfunction "SD1N0_106") (pintype "bidirectional"))
      (node (ref "R33") (pin "1") (pinfunction "1_1") (pintype "passive"))
    )
    (net (code "233") (name "V3+") (class "Default")
      (node (ref "C12") (pin "1") (pinfunction "1_1") (pintype "passive"))
      (node (ref "C3") (pin "1") (pinfunction "1_1") (pintype "passive"))
      (node (ref "MSP430F67791") (pin "107") (pinfunction "SD2P0_107") (pintype "bidirectional"))
      (node (ref "R18") (pin "1") (pinfunction "1_1") (pintype "passive"))
    )
    (net (code "234") (name "V3-") (class "Default")
      (node (ref "C12") (pin "2") (pinfunction "2_2") (pintype "passive"))
      (node (ref "C13") (pin "1") (pinfunction "1_1") (pintype "passive"))
      (node (ref "MSP430F67791") (pin "108") (pinfunction "SD2N0_108") (pintype "bidirectional"))
      (node (ref "R34") (pin "1") (pinfunction "1_1") (pintype "passive"))
    )
    (net (code "235") (name "VASYS1{slash}2") (class "Default")
      (node (ref "C22") (pin "1") (pinfunction "1_1") (pintype "passive"))
      (node (ref "C23") (pin "1") (pinfunction "1_1") (pintype "passive"))
      (node (ref "C28") (pin "1") (pinfunction "1_1") (pintype "passive"))
      (node (ref "C32") (pin "1") (pinfunction "1_1") (pintype "passive"))
      (node (ref "MSP430F67791") (pin "111") (pinfunction "VASYS2_111") (pintype "bidirectional"))
      (node (ref "MSP430F67791") (pin "122") (pinfunction "VASYS1_122") (pintype "bidirectional"))
    )
    (net (code "236") (name "VCC_ISO") (class "Default")
      (node (ref "C101") (pin "+") (pinfunction "+_+") (pintype "passive"))
      (node (ref "C42") (pin "1") (pinfunction "1_1") (pintype "passive"))
      (node (ref "JP3") (pin "1") (pinfunction "1_1") (pintype "passive"))
      (node (ref "U$1") (pin "VO+") (pinfunction "VO+_VO+") (pintype "bidirectional"))
      (node (ref "ZD3") (pin "C") (pinfunction "C_C") (pintype "passive"))
    )
    (net (code "237") (name "VCC_PL") (class "Default")
      (node (ref "C62") (pin "1") (pinfunction "1_1") (pintype "passive"))
      (node (ref "JP3") (pin "3") (pinfunction "3_3") (pintype "passive"))
      (node (ref "L7") (pin "2") (pinfunction "2_2") (pintype "passive"))
      (node (ref "R96") (pin "2") (pinfunction "2_2") (pintype "passive"))
    )
    (net (code "238") (name "VCORE") (class "Default")
      (node (ref "C38") (pin "1") (pinfunction "1_1") (pintype "passive"))
      (node (ref "MSP430F67791") (pin "128") (pinfunction "VCORE_128") (pintype "bidirectional"))
    )
    (net (code "239") (name "VMON") (class "Default")
      (node (ref "MSP430F67791") (pin "34") (pinfunction "P5.7/SD2DIO/CB2_34") (pintype "bidirectional"))
      (node (ref "R44") (pin "2") (pinfunction "2_2") (pintype "passive"))
      (node (ref "R45") (pin "1") (pinfunction "1_1") (pintype "passive"))
    )
    (net (code "240") (name "VREF") (class "Default")
      (node (ref "C30") (pin "1") (pinfunction "1_1") (pintype "passive"))
      (node (ref "MSP430F67791") (pin "113") (pinfunction "VREF_113") (pintype "bidirectional"))
    )
    (net (code "241") (name "VSUPPLY") (class "Default")
      (node (ref "C102") (pin "+") (pinfunction "+_+") (pintype "passive"))
      (node (ref "C48") (pin "1") (pinfunction "1_1") (pintype "passive"))
      (node (ref "D18") (pin "C") (pinfunction "C_C") (pintype "passive"))
      (node (ref "D20") (pin "C") (pinfunction "C_C") (pintype "passive"))
      (node (ref "D22") (pin "C") (pinfunction "C_C") (pintype "passive"))
      (node (ref "R35") (pin "2") (pinfunction "2_2") (pintype "passive"))
      (node (ref "R45") (pin "2") (pinfunction "2_2") (pintype "passive"))
      (node (ref "U3") (pin "2") (pinfunction "VIN_2") (pintype "input"))
    )
    (net (code "242") (name "XIN") (class "Default")
      (node (ref "C37") (pin "1") (pinfunction "1_1") (pintype "passive"))
      (node (ref "MSP430F67791") (pin "1") (pinfunction "XIN_1") (pintype "bidirectional"))
      (node (ref "XT1") (pin "P2") (pinfunction "2_P2") (pintype "bidirectional"))
    )
    (net (code "243") (name "XOUT") (class "Default")
      (node (ref "C40") (pin "1") (pinfunction "1_1") (pintype "passive"))
      (node (ref "MSP430F67791") (pin "2") (pinfunction "XOUT_2") (pintype "bidirectional"))
      (node (ref "XT1") (pin "P1") (pinfunction "1_P1") (pintype "bidirectional"))
    )
    (net (code "244") (name "unconnected-(EZ-RF-Pad3)") (class "Default")
      (node (ref "EZ-RF") (pin "3") (pinfunction "3_3") (pintype "passive"))
    )
    (net (code "245") (name "unconnected-(EZ-RF-Pad4)") (class "Default")
      (node (ref "EZ-RF") (pin "4") (pinfunction "4_4") (pintype "passive"))
    )
    (net (code "246") (name "unconnected-(JP6-Pad1)") (class "Default")
      (node (ref "JP6") (pin "1") (pinfunction "1_1") (pintype "passive"))
    )
    (net (code "247") (name "unconnected-(JP7-Pad1)") (class "Default")
      (node (ref "JP7") (pin "1") (pinfunction "1_1") (pintype "passive"))
    )
    (net (code "248") (name "unconnected-(JP8-Pad1)") (class "Default")
      (node (ref "JP8") (pin "1") (pinfunction "1_1") (pintype "passive"))
    )
    (net (code "249") (name "unconnected-(JP9-Pad1)") (class "Default")
      (node (ref "JP9") (pin "1") (pinfunction "1_1") (pintype "passive"))
    )
    (net (code "250") (name "unconnected-(JTAG-Pad6)") (class "Default")
      (node (ref "JTAG") (pin "6") (pinfunction "6_6") (pintype "passive"))
    )
    (net (code "251") (name "unconnected-(JTAG-Pad10)") (class "Default")
      (node (ref "JTAG") (pin "10") (pinfunction "10_10") (pintype "passive"))
    )
    (net (code "252") (name "unconnected-(JTAG-Pad12)") (class "Default")
      (node (ref "JTAG") (pin "12") (pinfunction "12_12") (pintype "passive"))
    )
    (net (code "253") (name "unconnected-(JTAG-Pad13)") (class "Default")
      (node (ref "JTAG") (pin "13") (pinfunction "13_13") (pintype "passive"))
    )
    (net (code "254") (name "unconnected-(JTAG-Pad14)") (class "Default")
      (node (ref "JTAG") (pin "14") (pinfunction "14_14") (pintype "passive"))
    )
    (net (code "255") (name "unconnected-(MSP430F67791-P1.3{slash}ADC10CLK{slash}A3-Pad8)") (class "Default")
      (node (ref "MSP430F67791") (pin "8") (pinfunction "P1.3/ADC10CLK/A3_8") (pintype "bidirectional"))
    )
    (net (code "256") (name "unconnected-(MSP430F67791-P3.2{slash}PM_UCA0CLK-Pad18)") (class "Default")
      (node (ref "MSP430F67791") (pin "18") (pinfunction "P3.2/PM_UCA0CLK_18") (pintype "bidirectional"))
    )
    (net (code "257") (name "unconnected-(MSP430F67791-P4.0{slash}PM_UCA2CLK-Pad38)") (class "Default")
      (node (ref "MSP430F67791") (pin "38") (pinfunction "P4.0/PM_UCA2CLK_38") (pintype "bidirectional"))
    )
    (net (code "258") (name "unconnected-(MSP430F67791-P6.0{slash}SD3DIO-Pad35)") (class "Default")
      (node (ref "MSP430F67791") (pin "35") (pinfunction "P6.0/SD3DIO_35") (pintype "bidirectional"))
    )
    (net (code "259") (name "unconnected-(RF1-Pad1)") (class "Default")
      (node (ref "RF1") (pin "1") (pinfunction "1_1") (pintype "passive"))
    )
    (net (code "260") (name "unconnected-(RF1-Pad3)") (class "Default")
      (node (ref "RF1") (pin "3") (pinfunction "3_3") (pintype "passive"))
    )
    (net (code "261") (name "unconnected-(RF1-Pad5)") (class "Default")
      (node (ref "RF1") (pin "5") (pinfunction "5_5") (pintype "passive"))
    )
    (net (code "262") (name "unconnected-(RF1-Pad8)") (class "Default")
      (node (ref "RF1") (pin "8") (pinfunction "8_8") (pintype "passive"))
    )
    (net (code "263") (name "unconnected-(RF1-Pad10)") (class "Default")
      (node (ref "RF1") (pin "10") (pinfunction "10_10") (pintype "passive"))
    )
    (net (code "264") (name "unconnected-(RF1-Pad11)") (class "Default")
      (node (ref "RF1") (pin "11") (pinfunction "11_11") (pintype "passive"))
    )
    (net (code "265") (name "unconnected-(RF1-Pad12)") (class "Default")
      (node (ref "RF1") (pin "12") (pinfunction "12_12") (pintype "passive"))
    )
    (net (code "266") (name "unconnected-(RF1-Pad13)") (class "Default")
      (node (ref "RF1") (pin "13") (pinfunction "13_13") (pintype "passive"))
    )
    (net (code "267") (name "unconnected-(RF1-Pad14)") (class "Default")
      (node (ref "RF1") (pin "14") (pinfunction "14_14") (pintype "passive"))
    )
    (net (code "268") (name "unconnected-(RF1-Pad16)") (class "Default")
      (node (ref "RF1") (pin "16") (pinfunction "16_16") (pintype "passive"))
    )
    (net (code "269") (name "unconnected-(RF1-Pad17)") (class "Default")
      (node (ref "RF1") (pin "17") (pinfunction "17_17") (pintype "passive"))
    )
    (net (code "270") (name "unconnected-(RF1-Pad20)") (class "Default")
      (node (ref "RF1") (pin "20") (pinfunction "20_20") (pintype "passive"))
    )
    (net (code "271") (name "unconnected-(RF2-Pad2)") (class "Default")
      (node (ref "RF2") (pin "2") (pinfunction "2_2") (pintype "passive"))
    )
    (net (code "272") (name "unconnected-(RF2-Pad4)") (class "Default")
      (node (ref "RF2") (pin "4") (pinfunction "4_4") (pintype "passive"))
    )
    (net (code "273") (name "unconnected-(RF2-Pad11)") (class "Default")
      (node (ref "RF2") (pin "11") (pinfunction "11_11") (pintype "passive"))
    )
    (net (code "274") (name "unconnected-(RF2-Pad13)") (class "Default")
      (node (ref "RF2") (pin "13") (pinfunction "13_13") (pintype "passive"))
    )
    (net (code "275") (name "unconnected-(RF2-Pad15)") (class "Default")
      (node (ref "RF2") (pin "15") (pinfunction "15_15") (pintype "passive"))
    )
    (net (code "276") (name "unconnected-(RF2-Pad17)") (class "Default")
      (node (ref "RF2") (pin "17") (pinfunction "17_17") (pintype "passive"))
    )
    (net (code "277") (name "unconnected-(RS-232-Pad1)") (class "Default")
      (node (ref "RS-232") (pin "1") (pinfunction "1_1") (pintype "passive"))
    )
    (net (code "278") (name "unconnected-(RS-232-Pad6)") (class "Default")
      (node (ref "RS-232") (pin "6") (pinfunction "6_6") (pintype "passive"))
    )
    (net (code "279") (name "unconnected-(RS-232-Pad8)") (class "Default")
      (node (ref "RS-232") (pin "8") (pinfunction "8_8") (pintype "passive"))
    )
    (net (code "280") (name "unconnected-(RS-232-Pad9)") (class "Default")
      (node (ref "RS-232") (pin "9") (pinfunction "9_9") (pintype "passive"))
    )
    (net (code "281") (name "unconnected-(U$1-PadNC)") (class "Default")
      (node (ref "U$1") (pin "NC") (pinfunction "NC_NC") (pintype "bidirectional"))
    )
    (net (code "282") (name "unconnected-(U2-VB-Pad7)") (class "Default")
      (node (ref "U2") (pin "7") (pinfunction "VB_7") (pintype "passive"))
    )
    (net (code "283") (name "unconnected-(U3-PWRGD-Pad6)") (class "Default")
      (node (ref "U3") (pin "6") (pinfunction "PWRGD_6") (pintype "output"))
    )
  )
)
